# Mem_Register_V1_0.net
KiCad netlist of a schematic drawn in EAGLE
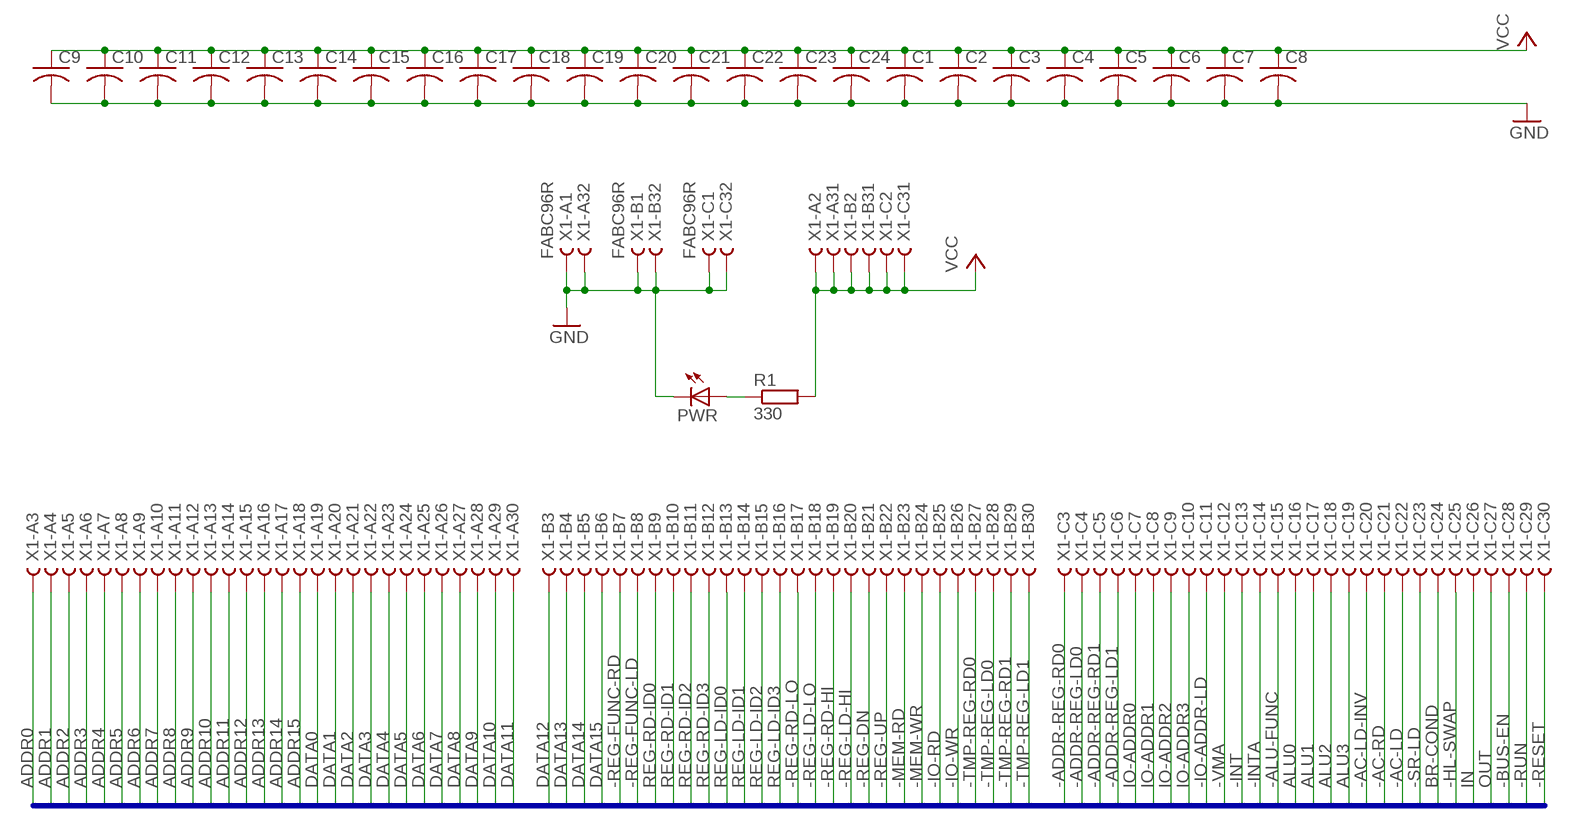
[diagram p0: schematic, sheet 1]
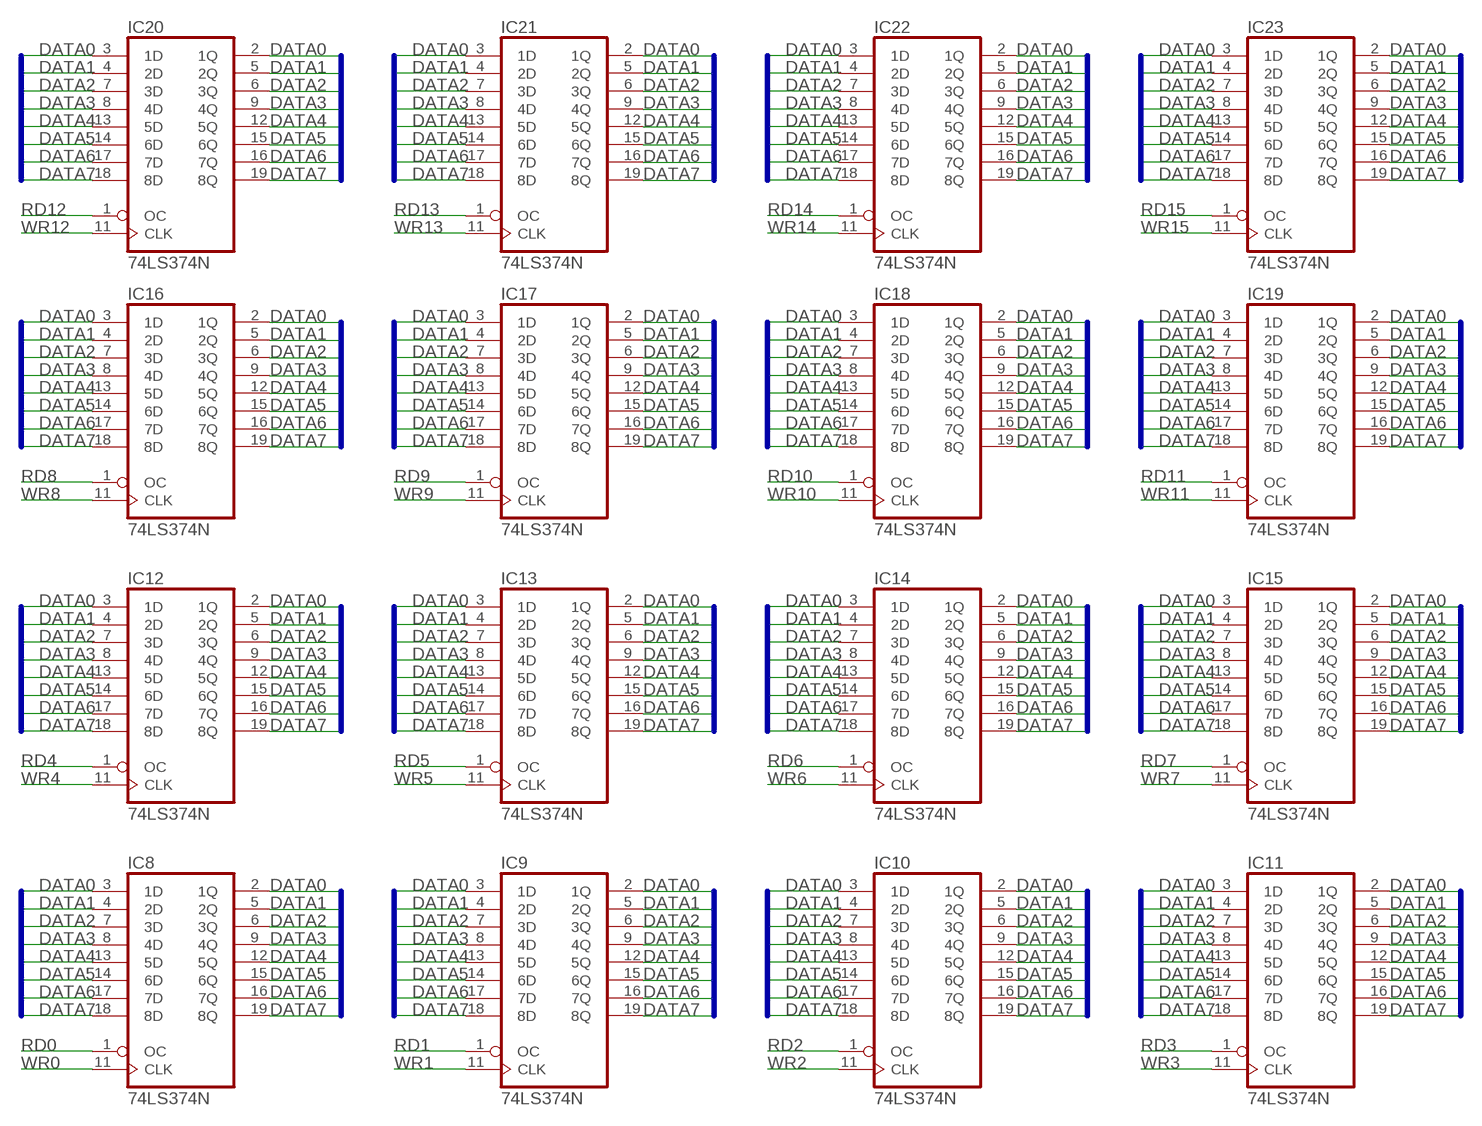
[diagram p1: schematic, sheet 2]
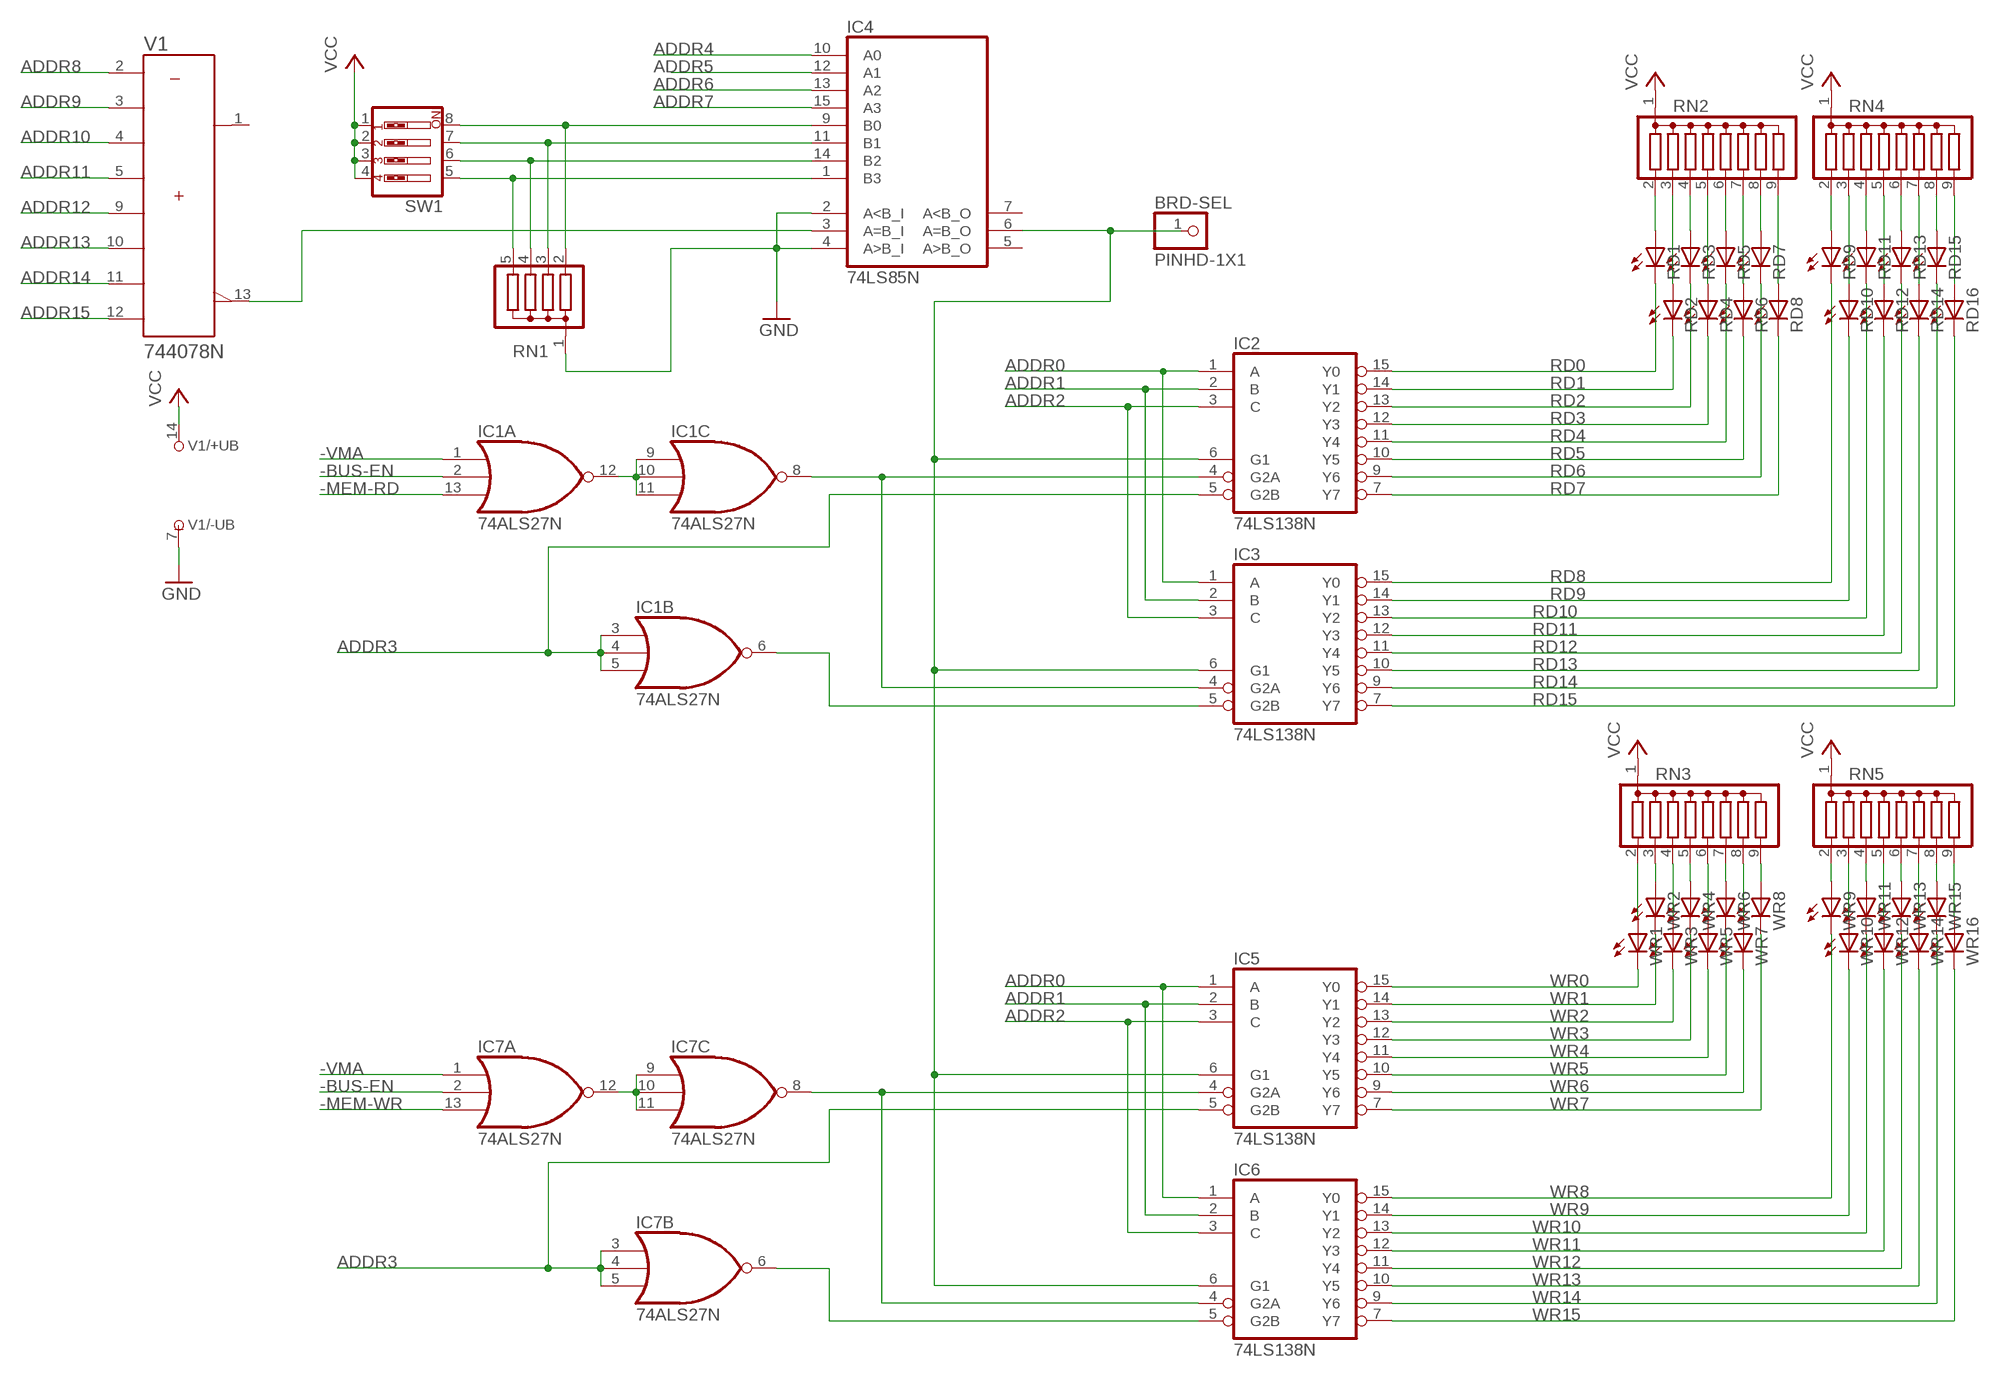
[diagram p2: schematic, sheet 3]

(export (version "E")
  (design (tool "Eeschema 10.0.6"))
  (components
    (comp (ref "C1")
      (value "C-US025-025X050")
      (footprint "eagle-import:C025-025X050")
      (libsource (lib "eagle-import") (part "C-US025-025X050"))
    )
    (comp (ref "C2")
      (value "C-US025-025X050")
      (footprint "eagle-import:C025-025X050")
      (libsource (lib "eagle-import") (part "C-US025-025X050"))
    )
    (comp (ref "C3")
      (value "C-US025-025X050")
      (footprint "eagle-import:C025-025X050")
      (libsource (lib "eagle-import") (part "C-US025-025X050"))
    )
    (comp (ref "C4")
      (value "C-US025-025X050")
      (footprint "eagle-import:C025-025X050")
      (libsource (lib "eagle-import") (part "C-US025-025X050"))
    )
    (comp (ref "C5")
      (value "C-US025-025X050")
      (footprint "eagle-import:C025-025X050")
      (libsource (lib "eagle-import") (part "C-US025-025X050"))
    )
    (comp (ref "C6")
      (value "C-US025-025X050")
      (footprint "eagle-import:C025-025X050")
      (libsource (lib "eagle-import") (part "C-US025-025X050"))
    )
    (comp (ref "C7")
      (value "C-US025-025X050")
      (footprint "eagle-import:C025-025X050")
      (libsource (lib "eagle-import") (part "C-US025-025X050"))
    )
    (comp (ref "C8")
      (value "C-US025-025X050")
      (footprint "eagle-import:C025-025X050")
      (libsource (lib "eagle-import") (part "C-US025-025X050"))
    )
    (comp (ref "C9")
      (value "C-US025-025X050")
      (footprint "eagle-import:C025-025X050")
      (libsource (lib "eagle-import") (part "C-US025-025X050"))
    )
    (comp (ref "C10")
      (value "C-US025-025X050")
      (footprint "eagle-import:C025-025X050")
      (libsource (lib "eagle-import") (part "C-US025-025X050"))
    )
    (comp (ref "C11")
      (value "C-US025-025X050")
      (footprint "eagle-import:C025-025X050")
      (libsource (lib "eagle-import") (part "C-US025-025X050"))
    )
    (comp (ref "C12")
      (value "C-US025-025X050")
      (footprint "eagle-import:C025-025X050")
      (libsource (lib "eagle-import") (part "C-US025-025X050"))
    )
    (comp (ref "C13")
      (value "C-US025-025X050")
      (footprint "eagle-import:C025-025X050")
      (libsource (lib "eagle-import") (part "C-US025-025X050"))
    )
    (comp (ref "C14")
      (value "C-US025-025X050")
      (footprint "eagle-import:C025-025X050")
      (libsource (lib "eagle-import") (part "C-US025-025X050"))
    )
    (comp (ref "C15")
      (value "C-US025-025X050")
      (footprint "eagle-import:C025-025X050")
      (libsource (lib "eagle-import") (part "C-US025-025X050"))
    )
    (comp (ref "C16")
      (value "C-US025-025X050")
      (footprint "eagle-import:C025-025X050")
      (libsource (lib "eagle-import") (part "C-US025-025X050"))
    )
    (comp (ref "C17")
      (value "C-US025-025X050")
      (footprint "eagle-import:C025-025X050")
      (libsource (lib "eagle-import") (part "C-US025-025X050"))
    )
    (comp (ref "C18")
      (value "C-US025-025X050")
      (footprint "eagle-import:C025-025X050")
      (libsource (lib "eagle-import") (part "C-US025-025X050"))
    )
    (comp (ref "C19")
      (value "C-US025-025X050")
      (footprint "eagle-import:C025-025X050")
      (libsource (lib "eagle-import") (part "C-US025-025X050"))
    )
    (comp (ref "C20")
      (value "C-US025-025X050")
      (footprint "eagle-import:C025-025X050")
      (libsource (lib "eagle-import") (part "C-US025-025X050"))
    )
    (comp (ref "C21")
      (value "C-US025-025X050")
      (footprint "eagle-import:C025-025X050")
      (libsource (lib "eagle-import") (part "C-US025-025X050"))
    )
    (comp (ref "C22")
      (value "C-US025-025X050")
      (footprint "eagle-import:C025-025X050")
      (libsource (lib "eagle-import") (part "C-US025-025X050"))
    )
    (comp (ref "C23")
      (value "C-US025-025X050")
      (footprint "eagle-import:C025-025X050")
      (libsource (lib "eagle-import") (part "C-US025-025X050"))
    )
    (comp (ref "C24")
      (value "C-US025-025X050")
      (footprint "eagle-import:C025-025X050")
      (libsource (lib "eagle-import") (part "C-US025-025X050"))
    )
    (comp (ref "PWR")
      (value "LED5MM")
      (footprint "eagle-import:LED5MM")
      (libsource (lib "eagle-import") (part "led_LED5MM"))
    )
    (comp (ref "R1")
      (value "330")
      (footprint "eagle-import:0207_10")
      (libsource (lib "eagle-import") (part "R0207/10"))
    )
    (comp (ref "X1")
      (value "FABC96R")
      (footprint "eagle-import:FABC96R")
      (libsource (lib "eagle-import") (part "FABC96R"))
    )
    (comp (ref "IC8")
      (value "74LS374N")
      (footprint "eagle-import:DIL20")
      (libsource (lib "eagle-import") (part "74374NLS"))
    )
    (comp (ref "IC9")
      (value "74LS374N")
      (footprint "eagle-import:DIL20")
      (libsource (lib "eagle-import") (part "74374NLS"))
    )
    (comp (ref "IC10")
      (value "74LS374N")
      (footprint "eagle-import:DIL20")
      (libsource (lib "eagle-import") (part "74374NLS"))
    )
    (comp (ref "IC11")
      (value "74LS374N")
      (footprint "eagle-import:DIL20")
      (libsource (lib "eagle-import") (part "74374NLS"))
    )
    (comp (ref "IC12")
      (value "74LS374N")
      (footprint "eagle-import:DIL20")
      (libsource (lib "eagle-import") (part "74374NLS"))
    )
    (comp (ref "IC13")
      (value "74LS374N")
      (footprint "eagle-import:DIL20")
      (libsource (lib "eagle-import") (part "74374NLS"))
    )
    (comp (ref "IC14")
      (value "74LS374N")
      (footprint "eagle-import:DIL20")
      (libsource (lib "eagle-import") (part "74374NLS"))
    )
    (comp (ref "IC15")
      (value "74LS374N")
      (footprint "eagle-import:DIL20")
      (libsource (lib "eagle-import") (part "74374NLS"))
    )
    (comp (ref "IC16")
      (value "74LS374N")
      (footprint "eagle-import:DIL20")
      (libsource (lib "eagle-import") (part "74374NLS"))
    )
    (comp (ref "IC17")
      (value "74LS374N")
      (footprint "eagle-import:DIL20")
      (libsource (lib "eagle-import") (part "74374NLS"))
    )
    (comp (ref "IC18")
      (value "74LS374N")
      (footprint "eagle-import:DIL20")
      (libsource (lib "eagle-import") (part "74374NLS"))
    )
    (comp (ref "IC19")
      (value "74LS374N")
      (footprint "eagle-import:DIL20")
      (libsource (lib "eagle-import") (part "74374NLS"))
    )
    (comp (ref "IC20")
      (value "74LS374N")
      (footprint "eagle-import:DIL20")
      (libsource (lib "eagle-import") (part "74374NLS"))
    )
    (comp (ref "IC21")
      (value "74LS374N")
      (footprint "eagle-import:DIL20")
      (libsource (lib "eagle-import") (part "74374NLS"))
    )
    (comp (ref "IC22")
      (value "74LS374N")
      (footprint "eagle-import:DIL20")
      (libsource (lib "eagle-import") (part "74374NLS"))
    )
    (comp (ref "IC23")
      (value "74LS374N")
      (footprint "eagle-import:DIL20")
      (libsource (lib "eagle-import") (part "74374NLS"))
    )
    (comp (ref "BRD-SEL")
      (value "PINHD-1X1")
      (footprint "eagle-import:1X01")
      (libsource (lib "eagle-import") (part "PINHD-1X1"))
    )
    (comp (ref "IC1")
      (value "74ALS27N")
      (footprint "eagle-import:DIL14")
      (libsource (lib "eagle-import") (part "7427NALS"))
    )
    (comp (ref "IC2")
      (value "74LS138N")
      (footprint "eagle-import:DIL16")
      (libsource (lib "eagle-import") (part "74138NLS"))
    )
    (comp (ref "IC3")
      (value "74LS138N")
      (footprint "eagle-import:DIL16")
      (libsource (lib "eagle-import") (part "74138NLS"))
    )
    (comp (ref "IC4")
      (value "74LS85N")
      (footprint "eagle-import:DIL16")
      (libsource (lib "eagle-import") (part "7485NLS"))
    )
    (comp (ref "IC5")
      (value "74LS138N")
      (footprint "eagle-import:DIL16")
      (libsource (lib "eagle-import") (part "74138NLS"))
    )
    (comp (ref "IC6")
      (value "74LS138N")
      (footprint "eagle-import:DIL16")
      (libsource (lib "eagle-import") (part "74138NLS"))
    )
    (comp (ref "IC7")
      (value "74ALS27N")
      (footprint "eagle-import:DIL14")
      (libsource (lib "eagle-import") (part "7427NALS"))
    )
    (comp (ref "RD1")
      (value "LED3MM")
      (footprint "eagle-import:LED3MM")
      (libsource (lib "eagle-import") (part "LED3MM"))
    )
    (comp (ref "RD2")
      (value "LED3MM")
      (footprint "eagle-import:LED3MM")
      (libsource (lib "eagle-import") (part "LED3MM"))
    )
    (comp (ref "RD3")
      (value "LED3MM")
      (footprint "eagle-import:LED3MM")
      (libsource (lib "eagle-import") (part "LED3MM"))
    )
    (comp (ref "RD4")
      (value "LED3MM")
      (footprint "eagle-import:LED3MM")
      (libsource (lib "eagle-import") (part "LED3MM"))
    )
    (comp (ref "RD5")
      (value "LED3MM")
      (footprint "eagle-import:LED3MM")
      (libsource (lib "eagle-import") (part "LED3MM"))
    )
    (comp (ref "RD6")
      (value "LED3MM")
      (footprint "eagle-import:LED3MM")
      (libsource (lib "eagle-import") (part "LED3MM"))
    )
    (comp (ref "RD7")
      (value "LED3MM")
      (footprint "eagle-import:LED3MM")
      (libsource (lib "eagle-import") (part "LED3MM"))
    )
    (comp (ref "RD8")
      (value "LED3MM")
      (footprint "eagle-import:LED3MM")
      (libsource (lib "eagle-import") (part "LED3MM"))
    )
    (comp (ref "RD9")
      (value "LED3MM")
      (footprint "eagle-import:LED3MM")
      (libsource (lib "eagle-import") (part "LED3MM"))
    )
    (comp (ref "RD10")
      (value "LED3MM")
      (footprint "eagle-import:LED3MM")
      (libsource (lib "eagle-import") (part "LED3MM"))
    )
    (comp (ref "RD11")
      (value "LED3MM")
      (footprint "eagle-import:LED3MM")
      (libsource (lib "eagle-import") (part "LED3MM"))
    )
    (comp (ref "RD12")
      (value "LED3MM")
      (footprint "eagle-import:LED3MM")
      (libsource (lib "eagle-import") (part "LED3MM"))
    )
    (comp (ref "RD13")
      (value "LED3MM")
      (footprint "eagle-import:LED3MM")
      (libsource (lib "eagle-import") (part "LED3MM"))
    )
    (comp (ref "RD14")
      (value "LED3MM")
      (footprint "eagle-import:LED3MM")
      (libsource (lib "eagle-import") (part "LED3MM"))
    )
    (comp (ref "RD15")
      (value "LED3MM")
      (footprint "eagle-import:LED3MM")
      (libsource (lib "eagle-import") (part "LED3MM"))
    )
    (comp (ref "RD16")
      (value "LED3MM")
      (footprint "eagle-import:LED3MM")
      (libsource (lib "eagle-import") (part "LED3MM"))
    )
    (comp (ref "RN1")
      (value "G04R")
      (footprint "eagle-import:SIL5")
      (libsource (lib "eagle-import") (part "G04R"))
    )
    (comp (ref "RN2")
      (value "G08R")
      (footprint "eagle-import:SIL9")
      (libsource (lib "eagle-import") (part "G08R"))
    )
    (comp (ref "RN3")
      (value "G08R")
      (footprint "eagle-import:SIL9")
      (libsource (lib "eagle-import") (part "G08R"))
    )
    (comp (ref "RN4")
      (value "G08R")
      (footprint "eagle-import:SIL9")
      (libsource (lib "eagle-import") (part "G08R"))
    )
    (comp (ref "RN5")
      (value "G08R")
      (footprint "eagle-import:SIL9")
      (libsource (lib "eagle-import") (part "G08R"))
    )
    (comp (ref "SW1")
      (value "SW_DIP-4")
      (footprint "eagle-import:EDG-04")
      (libsource (lib "eagle-import") (part "SW_DIP-4"))
    )
    (comp (ref "V1")
      (value "744078N")
      (footprint "eagle-import:DIL14")
      (libsource (lib "eagle-import") (part "744078N"))
    )
    (comp (ref "WR1")
      (value "LED3MM")
      (footprint "eagle-import:LED3MM")
      (libsource (lib "eagle-import") (part "LED3MM"))
    )
    (comp (ref "WR2")
      (value "LED3MM")
      (footprint "eagle-import:LED3MM")
      (libsource (lib "eagle-import") (part "LED3MM"))
    )
    (comp (ref "WR3")
      (value "LED3MM")
      (footprint "eagle-import:LED3MM")
      (libsource (lib "eagle-import") (part "LED3MM"))
    )
    (comp (ref "WR4")
      (value "LED3MM")
      (footprint "eagle-import:LED3MM")
      (libsource (lib "eagle-import") (part "LED3MM"))
    )
    (comp (ref "WR5")
      (value "LED3MM")
      (footprint "eagle-import:LED3MM")
      (libsource (lib "eagle-import") (part "LED3MM"))
    )
    (comp (ref "WR6")
      (value "LED3MM")
      (footprint "eagle-import:LED3MM")
      (libsource (lib "eagle-import") (part "LED3MM"))
    )
    (comp (ref "WR7")
      (value "LED3MM")
      (footprint "eagle-import:LED3MM")
      (libsource (lib "eagle-import") (part "LED3MM"))
    )
    (comp (ref "WR8")
      (value "LED3MM")
      (footprint "eagle-import:LED3MM")
      (libsource (lib "eagle-import") (part "LED3MM"))
    )
    (comp (ref "WR9")
      (value "LED3MM")
      (footprint "eagle-import:LED3MM")
      (libsource (lib "eagle-import") (part "LED3MM"))
    )
    (comp (ref "WR10")
      (value "LED3MM")
      (footprint "eagle-import:LED3MM")
      (libsource (lib "eagle-import") (part "LED3MM"))
    )
    (comp (ref "WR11")
      (value "LED3MM")
      (footprint "eagle-import:LED3MM")
      (libsource (lib "eagle-import") (part "LED3MM"))
    )
    (comp (ref "WR12")
      (value "LED3MM")
      (footprint "eagle-import:LED3MM")
      (libsource (lib "eagle-import") (part "LED3MM"))
    )
    (comp (ref "WR13")
      (value "LED3MM")
      (footprint "eagle-import:LED3MM")
      (libsource (lib "eagle-import") (part "LED3MM"))
    )
    (comp (ref "WR14")
      (value "LED3MM")
      (footprint "eagle-import:LED3MM")
      (libsource (lib "eagle-import") (part "LED3MM"))
    )
    (comp (ref "WR15")
      (value "LED3MM")
      (footprint "eagle-import:LED3MM")
      (libsource (lib "eagle-import") (part "LED3MM"))
    )
    (comp (ref "WR16")
      (value "LED3MM")
      (footprint "eagle-import:LED3MM")
      (libsource (lib "eagle-import") (part "LED3MM"))
    )
  )
  (nets
    (net (code "1") (name "-AC-LD") (class "Default")
      (node (ref "X1") (pin "C22") (pinfunction "B_C22") (pintype "passive"))
    )
    (net (code "2") (name "-AC-LD-INV") (class "Default")
      (node (ref "X1") (pin "C20") (pinfunction "B_C20") (pintype "passive"))
    )
    (net (code "3") (name "-AC-RD") (class "Default")
      (node (ref "X1") (pin "C21") (pinfunction "B_C21") (pintype "passive"))
    )
    (net (code "4") (name "-ADDR-REG-LD0") (class "Default")
      (node (ref "X1") (pin "C4") (pinfunction "B_C4") (pintype "passive"))
    )
    (net (code "5") (name "-ADDR-REG-LD1") (class "Default")
      (node (ref "X1") (pin "C6") (pinfunction "B_C6") (pintype "passive"))
    )
    (net (code "6") (name "-ADDR-REG-RD0") (class "Default")
      (node (ref "X1") (pin "C3") (pinfunction "B_C3") (pintype "passive"))
    )
    (net (code "7") (name "-ADDR-REG-RD1") (class "Default")
      (node (ref "X1") (pin "C5") (pinfunction "B_C5") (pintype "passive"))
    )
    (net (code "8") (name "-ALU-FUNC") (class "Default")
      (node (ref "X1") (pin "C15") (pinfunction "B_C15") (pintype "passive"))
    )
    (net (code "9") (name "-BUS-EN") (class "Default")
      (node (ref "IC1") (pin "2") (pinfunction "I1_2") (pintype "input"))
      (node (ref "IC7") (pin "2") (pinfunction "I1_2") (pintype "input"))
      (node (ref "X1") (pin "C28") (pinfunction "B_C28") (pintype "passive"))
    )
    (net (code "10") (name "-HL-SWAP") (class "Default")
      (node (ref "X1") (pin "C25") (pinfunction "B_C25") (pintype "passive"))
    )
    (net (code "11") (name "-INT") (class "Default")
      (node (ref "X1") (pin "C13") (pinfunction "B_C13") (pintype "passive"))
    )
    (net (code "12") (name "-INTA") (class "Default")
      (node (ref "X1") (pin "C14") (pinfunction "B_C14") (pintype "passive"))
    )
    (net (code "13") (name "-IO-ADDR-LD") (class "Default")
      (node (ref "X1") (pin "C11") (pinfunction "B_C11") (pintype "passive"))
    )
    (net (code "14") (name "-IO-RD") (class "Default")
      (node (ref "X1") (pin "B25") (pinfunction "B_B25") (pintype "passive"))
    )
    (net (code "15") (name "-IO-WR") (class "Default")
      (node (ref "X1") (pin "B26") (pinfunction "B_B26") (pintype "passive"))
    )
    (net (code "16") (name "-MEM-RD") (class "Default")
      (node (ref "IC1") (pin "13") (pinfunction "I2_13") (pintype "input"))
      (node (ref "X1") (pin "B23") (pinfunction "B_B23") (pintype "passive"))
    )
    (net (code "17") (name "-MEM-WR") (class "Default")
      (node (ref "IC7") (pin "13") (pinfunction "I2_13") (pintype "input"))
      (node (ref "X1") (pin "B24") (pinfunction "B_B24") (pintype "passive"))
    )
    (net (code "18") (name "-REG-DN") (class "Default")
      (node (ref "X1") (pin "B21") (pinfunction "B_B21") (pintype "passive"))
    )
    (net (code "19") (name "-REG-FUNC-LD") (class "Default")
      (node (ref "X1") (pin "B8") (pinfunction "B_B8") (pintype "passive"))
    )
    (net (code "20") (name "-REG-FUNC-RD") (class "Default")
      (node (ref "X1") (pin "B7") (pinfunction "B_B7") (pintype "passive"))
    )
    (net (code "21") (name "-REG-LD-HI") (class "Default")
      (node (ref "X1") (pin "B20") (pinfunction "B_B20") (pintype "passive"))
    )
    (net (code "22") (name "-REG-LD-LO") (class "Default")
      (node (ref "X1") (pin "B18") (pinfunction "B_B18") (pintype "passive"))
    )
    (net (code "23") (name "-REG-RD-HI") (class "Default")
      (node (ref "X1") (pin "B19") (pinfunction "B_B19") (pintype "passive"))
    )
    (net (code "24") (name "-REG-RD-LO") (class "Default")
      (node (ref "X1") (pin "B17") (pinfunction "B_B17") (pintype "passive"))
    )
    (net (code "25") (name "-REG-UP") (class "Default")
      (node (ref "X1") (pin "B22") (pinfunction "B_B22") (pintype "passive"))
    )
    (net (code "26") (name "-RESET") (class "Default")
      (node (ref "X1") (pin "C30") (pinfunction "B_C30") (pintype "passive"))
    )
    (net (code "27") (name "-RUN") (class "Default")
      (node (ref "X1") (pin "C29") (pinfunction "B_C29") (pintype "passive"))
    )
    (net (code "28") (name "-SR-LD") (class "Default")
      (node (ref "X1") (pin "C23") (pinfunction "B_C23") (pintype "passive"))
    )
    (net (code "29") (name "-TMP-REG-LD0") (class "Default")
      (node (ref "X1") (pin "B28") (pinfunction "B_B28") (pintype "passive"))
    )
    (net (code "30") (name "-TMP-REG-LD1") (class "Default")
      (node (ref "X1") (pin "B30") (pinfunction "B_B30") (pintype "passive"))
    )
    (net (code "31") (name "-TMP-REG-RD0") (class "Default")
      (node (ref "X1") (pin "B27") (pinfunction "B_B27") (pintype "passive"))
    )
    (net (code "32") (name "-TMP-REG-RD1") (class "Default")
      (node (ref "X1") (pin "B29") (pinfunction "B_B29") (pintype "passive"))
    )
    (net (code "33") (name "-VMA") (class "Default")
      (node (ref "IC1") (pin "1") (pinfunction "I0_1") (pintype "input"))
      (node (ref "IC7") (pin "1") (pinfunction "I0_1") (pintype "input"))
      (node (ref "X1") (pin "C12") (pinfunction "B_C12") (pintype "passive"))
    )
    (net (code "34") (name "ADDR0") (class "Default")
      (node (ref "IC2") (pin "1") (pinfunction "A_1") (pintype "input"))
      (node (ref "IC3") (pin "1") (pinfunction "A_1") (pintype "input"))
      (node (ref "IC5") (pin "1") (pinfunction "A_1") (pintype "input"))
      (node (ref "IC6") (pin "1") (pinfunction "A_1") (pintype "input"))
      (node (ref "X1") (pin "A3") (pinfunction "B_A3") (pintype "passive"))
    )
    (net (code "35") (name "ADDR1") (class "Default")
      (node (ref "IC2") (pin "2") (pinfunction "B_2") (pintype "input"))
      (node (ref "IC3") (pin "2") (pinfunction "B_2") (pintype "input"))
      (node (ref "IC5") (pin "2") (pinfunction "B_2") (pintype "input"))
      (node (ref "IC6") (pin "2") (pinfunction "B_2") (pintype "input"))
      (node (ref "X1") (pin "A4") (pinfunction "B_A4") (pintype "passive"))
    )
    (net (code "36") (name "ADDR2") (class "Default")
      (node (ref "IC2") (pin "3") (pinfunction "C_3") (pintype "input"))
      (node (ref "IC3") (pin "3") (pinfunction "C_3") (pintype "input"))
      (node (ref "IC5") (pin "3") (pinfunction "C_3") (pintype "input"))
      (node (ref "IC6") (pin "3") (pinfunction "C_3") (pintype "input"))
      (node (ref "X1") (pin "A5") (pinfunction "B_A5") (pintype "passive"))
    )
    (net (code "37") (name "ADDR3") (class "Default")
      (node (ref "IC1") (pin "3") (pinfunction "I0_3") (pintype "input"))
      (node (ref "IC1") (pin "4") (pinfunction "I1_4") (pintype "input"))
      (node (ref "IC1") (pin "5") (pinfunction "I2_5") (pintype "input"))
      (node (ref "IC2") (pin "5") (pinfunction "G2B_5") (pintype "input"))
      (node (ref "IC5") (pin "5") (pinfunction "G2B_5") (pintype "input"))
      (node (ref "IC7") (pin "3") (pinfunction "I0_3") (pintype "input"))
      (node (ref "IC7") (pin "4") (pinfunction "I1_4") (pintype "input"))
      (node (ref "IC7") (pin "5") (pinfunction "I2_5") (pintype "input"))
      (node (ref "X1") (pin "A6") (pinfunction "B_A6") (pintype "passive"))
    )
    (net (code "38") (name "ADDR4") (class "Default")
      (node (ref "IC4") (pin "10") (pinfunction "A0_10") (pintype "input"))
      (node (ref "X1") (pin "A7") (pinfunction "B_A7") (pintype "passive"))
    )
    (net (code "39") (name "ADDR5") (class "Default")
      (node (ref "IC4") (pin "12") (pinfunction "A1_12") (pintype "input"))
      (node (ref "X1") (pin "A8") (pinfunction "B_A8") (pintype "passive"))
    )
    (net (code "40") (name "ADDR6") (class "Default")
      (node (ref "IC4") (pin "13") (pinfunction "A2_13") (pintype "input"))
      (node (ref "X1") (pin "A9") (pinfunction "B_A9") (pintype "passive"))
    )
    (net (code "41") (name "ADDR7") (class "Default")
      (node (ref "IC4") (pin "15") (pinfunction "A3_15") (pintype "input"))
      (node (ref "X1") (pin "A10") (pinfunction "B_A10") (pintype "passive"))
    )
    (net (code "42") (name "ADDR8") (class "Default")
      (node (ref "V1") (pin "2") (pinfunction "A_2") (pintype "input"))
      (node (ref "X1") (pin "A11") (pinfunction "B_A11") (pintype "passive"))
    )
    (net (code "43") (name "ADDR9") (class "Default")
      (node (ref "V1") (pin "3") (pinfunction "B_3") (pintype "input"))
      (node (ref "X1") (pin "A12") (pinfunction "B_A12") (pintype "passive"))
    )
    (net (code "44") (name "ADDR10") (class "Default")
      (node (ref "V1") (pin "4") (pinfunction "C_4") (pintype "input"))
      (node (ref "X1") (pin "A13") (pinfunction "B_A13") (pintype "passive"))
    )
    (net (code "45") (name "ADDR11") (class "Default")
      (node (ref "V1") (pin "5") (pinfunction "D_5") (pintype "input"))
      (node (ref "X1") (pin "A14") (pinfunction "B_A14") (pintype "passive"))
    )
    (net (code "46") (name "ADDR12") (class "Default")
      (node (ref "V1") (pin "9") (pinfunction "E_9") (pintype "input"))
      (node (ref "X1") (pin "A15") (pinfunction "B_A15") (pintype "passive"))
    )
    (net (code "47") (name "ADDR13") (class "Default")
      (node (ref "V1") (pin "10") (pinfunction "F_10") (pintype "input"))
      (node (ref "X1") (pin "A16") (pinfunction "B_A16") (pintype "passive"))
    )
    (net (code "48") (name "ADDR14") (class "Default")
      (node (ref "V1") (pin "11") (pinfunction "G_11") (pintype "input"))
      (node (ref "X1") (pin "A17") (pinfunction "B_A17") (pintype "passive"))
    )
    (net (code "49") (name "ADDR15") (class "Default")
      (node (ref "V1") (pin "12") (pinfunction "H_12") (pintype "input"))
      (node (ref "X1") (pin "A18") (pinfunction "B_A18") (pintype "passive"))
    )
    (net (code "50") (name "ALU0") (class "Default")
      (node (ref "X1") (pin "C16") (pinfunction "B_C16") (pintype "passive"))
    )
    (net (code "51") (name "ALU1") (class "Default")
      (node (ref "X1") (pin "C17") (pinfunction "B_C17") (pintype "passive"))
    )
    (net (code "52") (name "ALU2") (class "Default")
      (node (ref "X1") (pin "C18") (pinfunction "B_C18") (pintype "passive"))
    )
    (net (code "53") (name "ALU3") (class "Default")
      (node (ref "X1") (pin "C19") (pinfunction "B_C19") (pintype "passive"))
    )
    (net (code "54") (name "BR-COND") (class "Default")
      (node (ref "X1") (pin "C24") (pinfunction "B_C24") (pintype "passive"))
    )
    (net (code "55") (name "DATA0") (class "Default")
      (node (ref "IC10") (pin "2") (pinfunction "1Q_2") (pintype "tri_state"))
      (node (ref "IC10") (pin "3") (pinfunction "1D_3") (pintype "input"))
      (node (ref "IC11") (pin "2") (pinfunction "1Q_2") (pintype "tri_state"))
      (node (ref "IC11") (pin "3") (pinfunction "1D_3") (pintype "input"))
      (node (ref "IC12") (pin "2") (pinfunction "1Q_2") (pintype "tri_state"))
      (node (ref "IC12") (pin "3") (pinfunction "1D_3") (pintype "input"))
      (node (ref "IC13") (pin "2") (pinfunction "1Q_2") (pintype "tri_state"))
      (node (ref "IC13") (pin "3") (pinfunction "1D_3") (pintype "input"))
      (node (ref "IC14") (pin "2") (pinfunction "1Q_2") (pintype "tri_state"))
      (node (ref "IC14") (pin "3") (pinfunction "1D_3") (pintype "input"))
      (node (ref "IC15") (pin "2") (pinfunction "1Q_2") (pintype "tri_state"))
      (node (ref "IC15") (pin "3") (pinfunction "1D_3") (pintype "input"))
      (node (ref "IC16") (pin "2") (pinfunction "1Q_2") (pintype "tri_state"))
      (node (ref "IC16") (pin "3") (pinfunction "1D_3") (pintype "input"))
      (node (ref "IC17") (pin "2") (pinfunction "1Q_2") (pintype "tri_state"))
      (node (ref "IC17") (pin "3") (pinfunction "1D_3") (pintype "input"))
      (node (ref "IC18") (pin "2") (pinfunction "1Q_2") (pintype "tri_state"))
      (node (ref "IC18") (pin "3") (pinfunction "1D_3") (pintype "input"))
      (node (ref "IC19") (pin "2") (pinfunction "1Q_2") (pintype "tri_state"))
      (node (ref "IC19") (pin "3") (pinfunction "1D_3") (pintype "input"))
      (node (ref "IC20") (pin "2") (pinfunction "1Q_2") (pintype "tri_state"))
      (node (ref "IC20") (pin "3") (pinfunction "1D_3") (pintype "input"))
      (node (ref "IC21") (pin "2") (pinfunction "1Q_2") (pintype "tri_state"))
      (node (ref "IC21") (pin "3") (pinfunction "1D_3") (pintype "input"))
      (node (ref "IC22") (pin "2") (pinfunction "1Q_2") (pintype "tri_state"))
      (node (ref "IC22") (pin "3") (pinfunction "1D_3") (pintype "input"))
      (node (ref "IC23") (pin "2") (pinfunction "1Q_2") (pintype "tri_state"))
      (node (ref "IC23") (pin "3") (pinfunction "1D_3") (pintype "input"))
      (node (ref "IC8") (pin "2") (pinfunction "1Q_2") (pintype "tri_state"))
      (node (ref "IC8") (pin "3") (pinfunction "1D_3") (pintype "input"))
      (node (ref "IC9") (pin "2") (pinfunction "1Q_2") (pintype "tri_state"))
      (node (ref "IC9") (pin "3") (pinfunction "1D_3") (pintype "input"))
      (node (ref "X1") (pin "A19") (pinfunction "B_A19") (pintype "passive"))
    )
    (net (code "56") (name "DATA1") (class "Default")
      (node (ref "IC10") (pin "4") (pinfunction "2D_4") (pintype "input"))
      (node (ref "IC10") (pin "5") (pinfunction "2Q_5") (pintype "tri_state"))
      (node (ref "IC11") (pin "4") (pinfunction "2D_4") (pintype "input"))
      (node (ref "IC11") (pin "5") (pinfunction "2Q_5") (pintype "tri_state"))
      (node (ref "IC12") (pin "4") (pinfunction "2D_4") (pintype "input"))
      (node (ref "IC12") (pin "5") (pinfunction "2Q_5") (pintype "tri_state"))
      (node (ref "IC13") (pin "4") (pinfunction "2D_4") (pintype "input"))
      (node (ref "IC13") (pin "5") (pinfunction "2Q_5") (pintype "tri_state"))
      (node (ref "IC14") (pin "4") (pinfunction "2D_4") (pintype "input"))
      (node (ref "IC14") (pin "5") (pinfunction "2Q_5") (pintype "tri_state"))
      (node (ref "IC15") (pin "4") (pinfunction "2D_4") (pintype "input"))
      (node (ref "IC15") (pin "5") (pinfunction "2Q_5") (pintype "tri_state"))
      (node (ref "IC16") (pin "4") (pinfunction "2D_4") (pintype "input"))
      (node (ref "IC16") (pin "5") (pinfunction "2Q_5") (pintype "tri_state"))
      (node (ref "IC17") (pin "4") (pinfunction "2D_4") (pintype "input"))
      (node (ref "IC17") (pin "5") (pinfunction "2Q_5") (pintype "tri_state"))
      (node (ref "IC18") (pin "4") (pinfunction "2D_4") (pintype "input"))
      (node (ref "IC18") (pin "5") (pinfunction "2Q_5") (pintype "tri_state"))
      (node (ref "IC19") (pin "4") (pinfunction "2D_4") (pintype "input"))
      (node (ref "IC19") (pin "5") (pinfunction "2Q_5") (pintype "tri_state"))
      (node (ref "IC20") (pin "4") (pinfunction "2D_4") (pintype "input"))
      (node (ref "IC20") (pin "5") (pinfunction "2Q_5") (pintype "tri_state"))
      (node (ref "IC21") (pin "4") (pinfunction "2D_4") (pintype "input"))
      (node (ref "IC21") (pin "5") (pinfunction "2Q_5") (pintype "tri_state"))
      (node (ref "IC22") (pin "4") (pinfunction "2D_4") (pintype "input"))
      (node (ref "IC22") (pin "5") (pinfunction "2Q_5") (pintype "tri_state"))
      (node (ref "IC23") (pin "4") (pinfunction "2D_4") (pintype "input"))
      (node (ref "IC23") (pin "5") (pinfunction "2Q_5") (pintype "tri_state"))
      (node (ref "IC8") (pin "4") (pinfunction "2D_4") (pintype "input"))
      (node (ref "IC8") (pin "5") (pinfunction "2Q_5") (pintype "tri_state"))
      (node (ref "IC9") (pin "4") (pinfunction "2D_4") (pintype "input"))
      (node (ref "IC9") (pin "5") (pinfunction "2Q_5") (pintype "tri_state"))
      (node (ref "X1") (pin "A20") (pinfunction "B_A20") (pintype "passive"))
    )
    (net (code "57") (name "DATA2") (class "Default")
      (node (ref "IC10") (pin "6") (pinfunction "3Q_6") (pintype "tri_state"))
      (node (ref "IC10") (pin "7") (pinfunction "3D_7") (pintype "input"))
      (node (ref "IC11") (pin "6") (pinfunction "3Q_6") (pintype "tri_state"))
      (node (ref "IC11") (pin "7") (pinfunction "3D_7") (pintype "input"))
      (node (ref "IC12") (pin "6") (pinfunction "3Q_6") (pintype "tri_state"))
      (node (ref "IC12") (pin "7") (pinfunction "3D_7") (pintype "input"))
      (node (ref "IC13") (pin "6") (pinfunction "3Q_6") (pintype "tri_state"))
      (node (ref "IC13") (pin "7") (pinfunction "3D_7") (pintype "input"))
      (node (ref "IC14") (pin "6") (pinfunction "3Q_6") (pintype "tri_state"))
      (node (ref "IC14") (pin "7") (pinfunction "3D_7") (pintype "input"))
      (node (ref "IC15") (pin "6") (pinfunction "3Q_6") (pintype "tri_state"))
      (node (ref "IC15") (pin "7") (pinfunction "3D_7") (pintype "input"))
      (node (ref "IC16") (pin "6") (pinfunction "3Q_6") (pintype "tri_state"))
      (node (ref "IC16") (pin "7") (pinfunction "3D_7") (pintype "input"))
      (node (ref "IC17") (pin "6") (pinfunction "3Q_6") (pintype "tri_state"))
      (node (ref "IC17") (pin "7") (pinfunction "3D_7") (pintype "input"))
      (node (ref "IC18") (pin "6") (pinfunction "3Q_6") (pintype "tri_state"))
      (node (ref "IC18") (pin "7") (pinfunction "3D_7") (pintype "input"))
      (node (ref "IC19") (pin "6") (pinfunction "3Q_6") (pintype "tri_state"))
      (node (ref "IC19") (pin "7") (pinfunction "3D_7") (pintype "input"))
      (node (ref "IC20") (pin "6") (pinfunction "3Q_6") (pintype "tri_state"))
      (node (ref "IC20") (pin "7") (pinfunction "3D_7") (pintype "input"))
      (node (ref "IC21") (pin "6") (pinfunction "3Q_6") (pintype "tri_state"))
      (node (ref "IC21") (pin "7") (pinfunction "3D_7") (pintype "input"))
      (node (ref "IC22") (pin "6") (pinfunction "3Q_6") (pintype "tri_state"))
      (node (ref "IC22") (pin "7") (pinfunction "3D_7") (pintype "input"))
      (node (ref "IC23") (pin "6") (pinfunction "3Q_6") (pintype "tri_state"))
      (node (ref "IC23") (pin "7") (pinfunction "3D_7") (pintype "input"))
      (node (ref "IC8") (pin "6") (pinfunction "3Q_6") (pintype "tri_state"))
      (node (ref "IC8") (pin "7") (pinfunction "3D_7") (pintype "input"))
      (node (ref "IC9") (pin "6") (pinfunction "3Q_6") (pintype "tri_state"))
      (node (ref "IC9") (pin "7") (pinfunction "3D_7") (pintype "input"))
      (node (ref "X1") (pin "A21") (pinfunction "B_A21") (pintype "passive"))
    )
    (net (code "58") (name "DATA3") (class "Default")
      (node (ref "IC10") (pin "8") (pinfunction "4D_8") (pintype "input"))
      (node (ref "IC10") (pin "9") (pinfunction "4Q_9") (pintype "tri_state"))
      (node (ref "IC11") (pin "8") (pinfunction "4D_8") (pintype "input"))
      (node (ref "IC11") (pin "9") (pinfunction "4Q_9") (pintype "tri_state"))
      (node (ref "IC12") (pin "8") (pinfunction "4D_8") (pintype "input"))
      (node (ref "IC12") (pin "9") (pinfunction "4Q_9") (pintype "tri_state"))
      (node (ref "IC13") (pin "8") (pinfunction "4D_8") (pintype "input"))
      (node (ref "IC13") (pin "9") (pinfunction "4Q_9") (pintype "tri_state"))
      (node (ref "IC14") (pin "8") (pinfunction "4D_8") (pintype "input"))
      (node (ref "IC14") (pin "9") (pinfunction "4Q_9") (pintype "tri_state"))
      (node (ref "IC15") (pin "8") (pinfunction "4D_8") (pintype "input"))
      (node (ref "IC15") (pin "9") (pinfunction "4Q_9") (pintype "tri_state"))
      (node (ref "IC16") (pin "8") (pinfunction "4D_8") (pintype "input"))
      (node (ref "IC16") (pin "9") (pinfunction "4Q_9") (pintype "tri_state"))
      (node (ref "IC17") (pin "8") (pinfunction "4D_8") (pintype "input"))
      (node (ref "IC17") (pin "9") (pinfunction "4Q_9") (pintype "tri_state"))
      (node (ref "IC18") (pin "8") (pinfunction "4D_8") (pintype "input"))
      (node (ref "IC18") (pin "9") (pinfunction "4Q_9") (pintype "tri_state"))
      (node (ref "IC19") (pin "8") (pinfunction "4D_8") (pintype "input"))
      (node (ref "IC19") (pin "9") (pinfunction "4Q_9") (pintype "tri_state"))
      (node (ref "IC20") (pin "8") (pinfunction "4D_8") (pintype "input"))
      (node (ref "IC20") (pin "9") (pinfunction "4Q_9") (pintype "tri_state"))
      (node (ref "IC21") (pin "8") (pinfunction "4D_8") (pintype "input"))
      (node (ref "IC21") (pin "9") (pinfunction "4Q_9") (pintype "tri_state"))
      (node (ref "IC22") (pin "8") (pinfunction "4D_8") (pintype "input"))
      (node (ref "IC22") (pin "9") (pinfunction "4Q_9") (pintype "tri_state"))
      (node (ref "IC23") (pin "8") (pinfunction "4D_8") (pintype "input"))
      (node (ref "IC23") (pin "9") (pinfunction "4Q_9") (pintype "tri_state"))
      (node (ref "IC8") (pin "8") (pinfunction "4D_8") (pintype "input"))
      (node (ref "IC8") (pin "9") (pinfunction "4Q_9") (pintype "tri_state"))
      (node (ref "IC9") (pin "8") (pinfunction "4D_8") (pintype "input"))
      (node (ref "IC9") (pin "9") (pinfunction "4Q_9") (pintype "tri_state"))
      (node (ref "X1") (pin "A22") (pinfunction "B_A22") (pintype "passive"))
    )
    (net (code "59") (name "DATA4") (class "Default")
      (node (ref "IC10") (pin "12") (pinfunction "5Q_12") (pintype "tri_state"))
      (node (ref "IC10") (pin "13") (pinfunction "5D_13") (pintype "input"))
      (node (ref "IC11") (pin "12") (pinfunction "5Q_12") (pintype "tri_state"))
      (node (ref "IC11") (pin "13") (pinfunction "5D_13") (pintype "input"))
      (node (ref "IC12") (pin "12") (pinfunction "5Q_12") (pintype "tri_state"))
      (node (ref "IC12") (pin "13") (pinfunction "5D_13") (pintype "input"))
      (node (ref "IC13") (pin "12") (pinfunction "5Q_12") (pintype "tri_state"))
      (node (ref "IC13") (pin "13") (pinfunction "5D_13") (pintype "input"))
      (node (ref "IC14") (pin "12") (pinfunction "5Q_12") (pintype "tri_state"))
      (node (ref "IC14") (pin "13") (pinfunction "5D_13") (pintype "input"))
      (node (ref "IC15") (pin "12") (pinfunction "5Q_12") (pintype "tri_state"))
      (node (ref "IC15") (pin "13") (pinfunction "5D_13") (pintype "input"))
      (node (ref "IC16") (pin "12") (pinfunction "5Q_12") (pintype "tri_state"))
      (node (ref "IC16") (pin "13") (pinfunction "5D_13") (pintype "input"))
      (node (ref "IC17") (pin "12") (pinfunction "5Q_12") (pintype "tri_state"))
      (node (ref "IC17") (pin "13") (pinfunction "5D_13") (pintype "input"))
      (node (ref "IC18") (pin "12") (pinfunction "5Q_12") (pintype "tri_state"))
      (node (ref "IC18") (pin "13") (pinfunction "5D_13") (pintype "input"))
      (node (ref "IC19") (pin "12") (pinfunction "5Q_12") (pintype "tri_state"))
      (node (ref "IC19") (pin "13") (pinfunction "5D_13") (pintype "input"))
      (node (ref "IC20") (pin "12") (pinfunction "5Q_12") (pintype "tri_state"))
      (node (ref "IC20") (pin "13") (pinfunction "5D_13") (pintype "input"))
      (node (ref "IC21") (pin "12") (pinfunction "5Q_12") (pintype "tri_state"))
      (node (ref "IC21") (pin "13") (pinfunction "5D_13") (pintype "input"))
      (node (ref "IC22") (pin "12") (pinfunction "5Q_12") (pintype "tri_state"))
      (node (ref "IC22") (pin "13") (pinfunction "5D_13") (pintype "input"))
      (node (ref "IC23") (pin "12") (pinfunction "5Q_12") (pintype "tri_state"))
      (node (ref "IC23") (pin "13") (pinfunction "5D_13") (pintype "input"))
      (node (ref "IC8") (pin "12") (pinfunction "5Q_12") (pintype "tri_state"))
      (node (ref "IC8") (pin "13") (pinfunction "5D_13") (pintype "input"))
      (node (ref "IC9") (pin "12") (pinfunction "5Q_12") (pintype "tri_state"))
      (node (ref "IC9") (pin "13") (pinfunction "5D_13") (pintype "input"))
      (node (ref "X1") (pin "A23") (pinfunction "B_A23") (pintype "passive"))
    )
    (net (code "60") (name "DATA5") (class "Default")
      (node (ref "IC10") (pin "14") (pinfunction "6D_14") (pintype "input"))
      (node (ref "IC10") (pin "15") (pinfunction "6Q_15") (pintype "tri_state"))
      (node (ref "IC11") (pin "14") (pinfunction "6D_14") (pintype "input"))
      (node (ref "IC11") (pin "15") (pinfunction "6Q_15") (pintype "tri_state"))
      (node (ref "IC12") (pin "14") (pinfunction "6D_14") (pintype "input"))
      (node (ref "IC12") (pin "15") (pinfunction "6Q_15") (pintype "tri_state"))
      (node (ref "IC13") (pin "14") (pinfunction "6D_14") (pintype "input"))
      (node (ref "IC13") (pin "15") (pinfunction "6Q_15") (pintype "tri_state"))
      (node (ref "IC14") (pin "14") (pinfunction "6D_14") (pintype "input"))
      (node (ref "IC14") (pin "15") (pinfunction "6Q_15") (pintype "tri_state"))
      (node (ref "IC15") (pin "14") (pinfunction "6D_14") (pintype "input"))
      (node (ref "IC15") (pin "15") (pinfunction "6Q_15") (pintype "tri_state"))
      (node (ref "IC16") (pin "14") (pinfunction "6D_14") (pintype "input"))
      (node (ref "IC16") (pin "15") (pinfunction "6Q_15") (pintype "tri_state"))
      (node (ref "IC17") (pin "14") (pinfunction "6D_14") (pintype "input"))
      (node (ref "IC17") (pin "15") (pinfunction "6Q_15") (pintype "tri_state"))
      (node (ref "IC18") (pin "14") (pinfunction "6D_14") (pintype "input"))
      (node (ref "IC18") (pin "15") (pinfunction "6Q_15") (pintype "tri_state"))
      (node (ref "IC19") (pin "14") (pinfunction "6D_14") (pintype "input"))
      (node (ref "IC19") (pin "15") (pinfunction "6Q_15") (pintype "tri_state"))
      (node (ref "IC20") (pin "14") (pinfunction "6D_14") (pintype "input"))
      (node (ref "IC20") (pin "15") (pinfunction "6Q_15") (pintype "tri_state"))
      (node (ref "IC21") (pin "14") (pinfunction "6D_14") (pintype "input"))
      (node (ref "IC21") (pin "15") (pinfunction "6Q_15") (pintype "tri_state"))
      (node (ref "IC22") (pin "14") (pinfunction "6D_14") (pintype "input"))
      (node (ref "IC22") (pin "15") (pinfunction "6Q_15") (pintype "tri_state"))
      (node (ref "IC23") (pin "14") (pinfunction "6D_14") (pintype "input"))
      (node (ref "IC23") (pin "15") (pinfunction "6Q_15") (pintype "tri_state"))
      (node (ref "IC8") (pin "14") (pinfunction "6D_14") (pintype "input"))
      (node (ref "IC8") (pin "15") (pinfunction "6Q_15") (pintype "tri_state"))
      (node (ref "IC9") (pin "14") (pinfunction "6D_14") (pintype "input"))
      (node (ref "IC9") (pin "15") (pinfunction "6Q_15") (pintype "tri_state"))
      (node (ref "X1") (pin "A24") (pinfunction "B_A24") (pintype "passive"))
    )
    (net (code "61") (name "DATA6") (class "Default")
      (node (ref "IC10") (pin "16") (pinfunction "7Q_16") (pintype "tri_state"))
      (node (ref "IC10") (pin "17") (pinfunction "7D_17") (pintype "input"))
      (node (ref "IC11") (pin "16") (pinfunction "7Q_16") (pintype "tri_state"))
      (node (ref "IC11") (pin "17") (pinfunction "7D_17") (pintype "input"))
      (node (ref "IC12") (pin "16") (pinfunction "7Q_16") (pintype "tri_state"))
      (node (ref "IC12") (pin "17") (pinfunction "7D_17") (pintype "input"))
      (node (ref "IC13") (pin "16") (pinfunction "7Q_16") (pintype "tri_state"))
      (node (ref "IC13") (pin "17") (pinfunction "7D_17") (pintype "input"))
      (node (ref "IC14") (pin "16") (pinfunction "7Q_16") (pintype "tri_state"))
      (node (ref "IC14") (pin "17") (pinfunction "7D_17") (pintype "input"))
      (node (ref "IC15") (pin "16") (pinfunction "7Q_16") (pintype "tri_state"))
      (node (ref "IC15") (pin "17") (pinfunction "7D_17") (pintype "input"))
      (node (ref "IC16") (pin "16") (pinfunction "7Q_16") (pintype "tri_state"))
      (node (ref "IC16") (pin "17") (pinfunction "7D_17") (pintype "input"))
      (node (ref "IC17") (pin "16") (pinfunction "7Q_16") (pintype "tri_state"))
      (node (ref "IC17") (pin "17") (pinfunction "7D_17") (pintype "input"))
      (node (ref "IC18") (pin "16") (pinfunction "7Q_16") (pintype "tri_state"))
      (node (ref "IC18") (pin "17") (pinfunction "7D_17") (pintype "input"))
      (node (ref "IC19") (pin "16") (pinfunction "7Q_16") (pintype "tri_state"))
      (node (ref "IC19") (pin "17") (pinfunction "7D_17") (pintype "input"))
      (node (ref "IC20") (pin "16") (pinfunction "7Q_16") (pintype "tri_state"))
      (node (ref "IC20") (pin "17") (pinfunction "7D_17") (pintype "input"))
      (node (ref "IC21") (pin "16") (pinfunction "7Q_16") (pintype "tri_state"))
      (node (ref "IC21") (pin "17") (pinfunction "7D_17") (pintype "input"))
      (node (ref "IC22") (pin "16") (pinfunction "7Q_16") (pintype "tri_state"))
      (node (ref "IC22") (pin "17") (pinfunction "7D_17") (pintype "input"))
      (node (ref "IC23") (pin "16") (pinfunction "7Q_16") (pintype "tri_state"))
      (node (ref "IC23") (pin "17") (pinfunction "7D_17") (pintype "input"))
      (node (ref "IC8") (pin "16") (pinfunction "7Q_16") (pintype "tri_state"))
      (node (ref "IC8") (pin "17") (pinfunction "7D_17") (pintype "input"))
      (node (ref "IC9") (pin "16") (pinfunction "7Q_16") (pintype "tri_state"))
      (node (ref "IC9") (pin "17") (pinfunction "7D_17") (pintype "input"))
      (node (ref "X1") (pin "A25") (pinfunction "B_A25") (pintype "passive"))
    )
    (net (code "62") (name "DATA7") (class "Default")
      (node (ref "IC10") (pin "18") (pinfunction "8D_18") (pintype "input"))
      (node (ref "IC10") (pin "19") (pinfunction "8Q_19") (pintype "tri_state"))
      (node (ref "IC11") (pin "18") (pinfunction "8D_18") (pintype "input"))
      (node (ref "IC11") (pin "19") (pinfunction "8Q_19") (pintype "tri_state"))
      (node (ref "IC12") (pin "18") (pinfunction "8D_18") (pintype "input"))
      (node (ref "IC12") (pin "19") (pinfunction "8Q_19") (pintype "tri_state"))
      (node (ref "IC13") (pin "18") (pinfunction "8D_18") (pintype "input"))
      (node (ref "IC13") (pin "19") (pinfunction "8Q_19") (pintype "tri_state"))
      (node (ref "IC14") (pin "18") (pinfunction "8D_18") (pintype "input"))
      (node (ref "IC14") (pin "19") (pinfunction "8Q_19") (pintype "tri_state"))
      (node (ref "IC15") (pin "18") (pinfunction "8D_18") (pintype "input"))
      (node (ref "IC15") (pin "19") (pinfunction "8Q_19") (pintype "tri_state"))
      (node (ref "IC16") (pin "18") (pinfunction "8D_18") (pintype "input"))
      (node (ref "IC16") (pin "19") (pinfunction "8Q_19") (pintype "tri_state"))
      (node (ref "IC17") (pin "18") (pinfunction "8D_18") (pintype "input"))
      (node (ref "IC17") (pin "19") (pinfunction "8Q_19") (pintype "tri_state"))
      (node (ref "IC18") (pin "18") (pinfunction "8D_18") (pintype "input"))
      (node (ref "IC18") (pin "19") (pinfunction "8Q_19") (pintype "tri_state"))
      (node (ref "IC19") (pin "18") (pinfunction "8D_18") (pintype "input"))
      (node (ref "IC19") (pin "19") (pinfunction "8Q_19") (pintype "tri_state"))
      (node (ref "IC20") (pin "18") (pinfunction "8D_18") (pintype "input"))
      (node (ref "IC20") (pin "19") (pinfunction "8Q_19") (pintype "tri_state"))
      (node (ref "IC21") (pin "18") (pinfunction "8D_18") (pintype "input"))
      (node (ref "IC21") (pin "19") (pinfunction "8Q_19") (pintype "tri_state"))
      (node (ref "IC22") (pin "18") (pinfunction "8D_18") (pintype "input"))
      (node (ref "IC22") (pin "19") (pinfunction "8Q_19") (pintype "tri_state"))
      (node (ref "IC23") (pin "18") (pinfunction "8D_18") (pintype "input"))
      (node (ref "IC23") (pin "19") (pinfunction "8Q_19") (pintype "tri_state"))
      (node (ref "IC8") (pin "18") (pinfunction "8D_18") (pintype "input"))
      (node (ref "IC8") (pin "19") (pinfunction "8Q_19") (pintype "tri_state"))
      (node (ref "IC9") (pin "18") (pinfunction "8D_18") (pintype "input"))
      (node (ref "IC9") (pin "19") (pinfunction "8Q_19") (pintype "tri_state"))
      (node (ref "X1") (pin "A26") (pinfunction "B_A26") (pintype "passive"))
    )
    (net (code "63") (name "DATA8") (class "Default")
      (node (ref "X1") (pin "A27") (pinfunction "B_A27") (pintype "passive"))
    )
    (net (code "64") (name "DATA9") (class "Default")
      (node (ref "X1") (pin "A28") (pinfunction "B_A28") (pintype "passive"))
    )
    (net (code "65") (name "DATA10") (class "Default")
      (node (ref "X1") (pin "A29") (pinfunction "B_A29") (pintype "passive"))
    )
    (net (code "66") (name "DATA11") (class "Default")
      (node (ref "X1") (pin "A30") (pinfunction "B_A30") (pintype "passive"))
    )
    (net (code "67") (name "DATA12") (class "Default")
      (node (ref "X1") (pin "B3") (pinfunction "B_B3") (pintype "passive"))
    )
    (net (code "68") (name "DATA13") (class "Default")
      (node (ref "X1") (pin "B4") (pinfunction "B_B4") (pintype "passive"))
    )
    (net (code "69") (name "DATA14") (class "Default")
      (node (ref "X1") (pin "B5") (pinfunction "B_B5") (pintype "passive"))
    )
    (net (code "70") (name "DATA15") (class "Default")
      (node (ref "X1") (pin "B6") (pinfunction "B_B6") (pintype "passive"))
    )
    (net (code "71") (name "GND") (class "Default")
      (node (ref "C1") (pin "2") (pinfunction "2_2") (pintype "passive"))
      (node (ref "C10") (pin "2") (pinfunction "2_2") (pintype "passive"))
      (node (ref "C11") (pin "2") (pinfunction "2_2") (pintype "passive"))
      (node (ref "C12") (pin "2") (pinfunction "2_2") (pintype "passive"))
      (node (ref "C13") (pin "2") (pinfunction "2_2") (pintype "passive"))
      (node (ref "C14") (pin "2") (pinfunction "2_2") (pintype "passive"))
      (node (ref "C15") (pin "2") (pinfunction "2_2") (pintype "passive"))
      (node (ref "C16") (pin "2") (pinfunction "2_2") (pintype "passive"))
      (node (ref "C17") (pin "2") (pinfunction "2_2") (pintype "passive"))
      (node (ref "C18") (pin "2") (pinfunction "2_2") (pintype "passive"))
      (node (ref "C19") (pin "2") (pinfunction "2_2") (pintype "passive"))
      (node (ref "C2") (pin "2") (pinfunction "2_2") (pintype "passive"))
      (node (ref "C20") (pin "2") (pinfunction "2_2") (pintype "passive"))
      (node (ref "C21") (pin "2") (pinfunction "2_2") (pintype "passive"))
      (node (ref "C22") (pin "2") (pinfunction "2_2") (pintype "passive"))
      (node (ref "C23") (pin "2") (pinfunction "2_2") (pintype "passive"))
      (node (ref "C24") (pin "2") (pinfunction "2_2") (pintype "passive"))
      (node (ref "C3") (pin "2") (pinfunction "2_2") (pintype "passive"))
      (node (ref "C4") (pin "2") (pinfunction "2_2") (pintype "passive"))
      (node (ref "C5") (pin "2") (pinfunction "2_2") (pintype "passive"))
      (node (ref "C6") (pin "2") (pinfunction "2_2") (pintype "passive"))
      (node (ref "C7") (pin "2") (pinfunction "2_2") (pintype "passive"))
      (node (ref "C8") (pin "2") (pinfunction "2_2") (pintype "passive"))
      (node (ref "C9") (pin "2") (pinfunction "2_2") (pintype "passive"))
      (node (ref "IC4") (pin "2") (pinfunction "A<B_I_2") (pintype "input"))
      (node (ref "IC4") (pin "4") (pinfunction "A>B_I_4") (pintype "input"))
      (node (ref "PWR") (pin "K") (pinfunction "C_K") (pintype "passive"))
      (node (ref "RN1") (pin "1") (pinfunction "1_1") (pintype "passive"))
      (node (ref "V1") (pin "7") (pinfunction "-UB_7") (pintype "power_in"))
      (node (ref "X1") (pin "A1") (pinfunction "B_A1") (pintype "passive"))
      (node (ref "X1") (pin "A32") (pinfunction "B_A32") (pintype "passive"))
      (node (ref "X1") (pin "B1") (pinfunction "B_B1") (pintype "passive"))
      (node (ref "X1") (pin "B32") (pinfunction "B_B32") (pintype "passive"))
      (node (ref "X1") (pin "C1") (pinfunction "B_C1") (pintype "passive"))
      (node (ref "X1") (pin "C32") (pinfunction "B_C32") (pintype "passive"))
    )
    (net (code "72") (name "IN") (class "Default")
      (node (ref "X1") (pin "C26") (pinfunction "B_C26") (pintype "passive"))
    )
    (net (code "73") (name "IO-ADDR0") (class "Default")
      (node (ref "X1") (pin "C7") (pinfunction "B_C7") (pintype "passive"))
    )
    (net (code "74") (name "IO-ADDR1") (class "Default")
      (node (ref "X1") (pin "C8") (pinfunction "B_C8") (pintype "passive"))
    )
    (net (code "75") (name "IO-ADDR2") (class "Default")
      (node (ref "X1") (pin "C9") (pinfunction "B_C9") (pintype "passive"))
    )
    (net (code "76") (name "IO-ADDR3") (class "Default")
      (node (ref "X1") (pin "C10") (pinfunction "B_C10") (pintype "passive"))
    )
    (net (code "77") (name "Net-(IC1A-O)") (class "Default")
      (node (ref "IC1") (pin "10") (pinfunction "I1_10") (pintype "input"))
      (node (ref "IC1") (pin "11") (pinfunction "I2_11") (pintype "input"))
      (node (ref "IC1") (pin "12") (pinfunction "O_12") (pintype "output"))
      (node (ref "IC1") (pin "9") (pinfunction "I0_9") (pintype "input"))
    )
    (net (code "78") (name "Net-(IC1B-O)") (class "Default")
      (node (ref "IC1") (pin "6") (pinfunction "O_6") (pintype "output"))
      (node (ref "IC3") (pin "5") (pinfunction "G2B_5") (pintype "input"))
    )
    (net (code "79") (name "Net-(IC1C-O)") (class "Default")
      (node (ref "IC1") (pin "8") (pinfunction "O_8") (pintype "output"))
      (node (ref "IC2") (pin "4") (pinfunction "G2A_4") (pintype "input"))
      (node (ref "IC3") (pin "4") (pinfunction "G2A_4") (pintype "input"))
    )
    (net (code "80") (name "Net-(IC2A-G1)") (class "Default")
      (node (ref "BRD-SEL") (pin "1") (pinfunction "1_1") (pintype "passive"))
      (node (ref "IC2") (pin "6") (pinfunction "G1_6") (pintype "input"))
      (node (ref "IC3") (pin "6") (pinfunction "G1_6") (pintype "input"))
      (node (ref "IC4") (pin "6") (pinfunction "A=B_O_6") (pintype "output"))
      (node (ref "IC5") (pin "6") (pinfunction "G1_6") (pintype "input"))
      (node (ref "IC6") (pin "6") (pinfunction "G1_6") (pintype "input"))
    )
    (net (code "81") (name "Net-(IC4A-A=B_I)") (class "Default")
      (node (ref "IC4") (pin "3") (pinfunction "A=B_I_3") (pintype "input"))
      (node (ref "V1") (pin "13") (pinfunction "W_13") (pintype "output"))
    )
    (net (code "82") (name "Net-(IC4A-B0)") (class "Default")
      (node (ref "IC4") (pin "9") (pinfunction "B0_9") (pintype "input"))
      (node (ref "RN1") (pin "2") (pinfunction "2_2") (pintype "passive"))
      (node (ref "SW1") (pin "8") (pinfunction "8_8") (pintype "passive"))
    )
    (net (code "83") (name "Net-(IC4A-B1)") (class "Default")
      (node (ref "IC4") (pin "11") (pinfunction "B1_11") (pintype "input"))
      (node (ref "RN1") (pin "3") (pinfunction "3_3") (pintype "passive"))
      (node (ref "SW1") (pin "7") (pinfunction "7_7") (pintype "passive"))
    )
    (net (code "84") (name "Net-(IC4A-B2)") (class "Default")
      (node (ref "IC4") (pin "14") (pinfunction "B2_14") (pintype "input"))
      (node (ref "RN1") (pin "4") (pinfunction "4_4") (pintype "passive"))
      (node (ref "SW1") (pin "6") (pinfunction "6_6") (pintype "passive"))
    )
    (net (code "85") (name "Net-(IC4A-B3)") (class "Default")
      (node (ref "IC4") (pin "1") (pinfunction "B3_1") (pintype "input"))
      (node (ref "RN1") (pin "5") (pinfunction "5_5") (pintype "passive"))
      (node (ref "SW1") (pin "5") (pinfunction "5_5") (pintype "passive"))
    )
    (net (code "86") (name "Net-(IC5A-G2A)") (class "Default")
      (node (ref "IC5") (pin "4") (pinfunction "G2A_4") (pintype "input"))
      (node (ref "IC6") (pin "4") (pinfunction "G2A_4") (pintype "input"))
      (node (ref "IC7") (pin "8") (pinfunction "O_8") (pintype "output"))
    )
    (net (code "87") (name "Net-(IC6A-G2B)") (class "Default")
      (node (ref "IC6") (pin "5") (pinfunction "G2B_5") (pintype "input"))
      (node (ref "IC7") (pin "6") (pinfunction "O_6") (pintype "output"))
    )
    (net (code "88") (name "Net-(IC7A-O)") (class "Default")
      (node (ref "IC7") (pin "10") (pinfunction "I1_10") (pintype "input"))
      (node (ref "IC7") (pin "11") (pinfunction "I2_11") (pintype "input"))
      (node (ref "IC7") (pin "12") (pinfunction "O_12") (pintype "output"))
      (node (ref "IC7") (pin "9") (pinfunction "I0_9") (pintype "input"))
    )
    (net (code "89") (name "Net-(PWR-PadA)") (class "Default")
      (node (ref "PWR") (pin "A") (pinfunction "A_A") (pintype "passive"))
      (node (ref "R1") (pin "1") (pinfunction "1_1") (pintype "passive"))
    )
    (net (code "90") (name "Net-(RD1-PadA)") (class "Default")
      (node (ref "RD1") (pin "A") (pinfunction "A_A") (pintype "passive"))
      (node (ref "RN2") (pin "2") (pinfunction "2_2") (pintype "passive"))
    )
    (net (code "91") (name "Net-(RD2-PadA)") (class "Default")
      (node (ref "RD2") (pin "A") (pinfunction "A_A") (pintype "passive"))
      (node (ref "RN2") (pin "3") (pinfunction "3_3") (pintype "passive"))
    )
    (net (code "92") (name "Net-(RD3-PadA)") (class "Default")
      (node (ref "RD3") (pin "A") (pinfunction "A_A") (pintype "passive"))
      (node (ref "RN2") (pin "4") (pinfunction "4_4") (pintype "passive"))
    )
    (net (code "93") (name "Net-(RD4-PadA)") (class "Default")
      (node (ref "RD4") (pin "A") (pinfunction "A_A") (pintype "passive"))
      (node (ref "RN2") (pin "5") (pinfunction "5_5") (pintype "passive"))
    )
    (net (code "94") (name "Net-(RD5-PadA)") (class "Default")
      (node (ref "RD5") (pin "A") (pinfunction "A_A") (pintype "passive"))
      (node (ref "RN2") (pin "6") (pinfunction "6_6") (pintype "passive"))
    )
    (net (code "95") (name "Net-(RD6-PadA)") (class "Default")
      (node (ref "RD6") (pin "A") (pinfunction "A_A") (pintype "passive"))
      (node (ref "RN2") (pin "7") (pinfunction "7_7") (pintype "passive"))
    )
    (net (code "96") (name "Net-(RD7-PadA)") (class "Default")
      (node (ref "RD7") (pin "A") (pinfunction "A_A") (pintype "passive"))
      (node (ref "RN2") (pin "8") (pinfunction "8_8") (pintype "passive"))
    )
    (net (code "97") (name "Net-(RD8-PadA)") (class "Default")
      (node (ref "RD8") (pin "A") (pinfunction "A_A") (pintype "passive"))
      (node (ref "RN2") (pin "9") (pinfunction "9_9") (pintype "passive"))
    )
    (net (code "98") (name "Net-(RD9-PadA)") (class "Default")
      (node (ref "RD9") (pin "A") (pinfunction "A_A") (pintype "passive"))
      (node (ref "RN4") (pin "2") (pinfunction "2_2") (pintype "passive"))
    )
    (net (code "99") (name "Net-(RD10-PadA)") (class "Default")
      (node (ref "RD10") (pin "A") (pinfunction "A_A") (pintype "passive"))
      (node (ref "RN4") (pin "3") (pinfunction "3_3") (pintype "passive"))
    )
    (net (code "100") (name "Net-(RD11-PadA)") (class "Default")
      (node (ref "RD11") (pin "A") (pinfunction "A_A") (pintype "passive"))
      (node (ref "RN4") (pin "4") (pinfunction "4_4") (pintype "passive"))
    )
    (net (code "101") (name "Net-(RD12-PadA)") (class "Default")
      (node (ref "RD12") (pin "A") (pinfunction "A_A") (pintype "passive"))
      (node (ref "RN4") (pin "5") (pinfunction "5_5") (pintype "passive"))
    )
    (net (code "102") (name "Net-(RD13-PadA)") (class "Default")
      (node (ref "RD13") (pin "A") (pinfunction "A_A") (pintype "passive"))
      (node (ref "RN4") (pin "6") (pinfunction "6_6") (pintype "passive"))
    )
    (net (code "103") (name "Net-(RD14-PadA)") (class "Default")
      (node (ref "RD14") (pin "A") (pinfunction "A_A") (pintype "passive"))
      (node (ref "RN4") (pin "7") (pinfunction "7_7") (pintype "passive"))
    )
    (net (code "104") (name "Net-(RD15-PadA)") (class "Default")
      (node (ref "RD15") (pin "A") (pinfunction "A_A") (pintype "passive"))
      (node (ref "RN4") (pin "8") (pinfunction "8_8") (pintype "passive"))
    )
    (net (code "105") (name "Net-(RD16-PadA)") (class "Default")
      (node (ref "RD16") (pin "A") (pinfunction "A_A") (pintype "passive"))
      (node (ref "RN4") (pin "9") (pinfunction "9_9") (pintype "passive"))
    )
    (net (code "106") (name "Net-(RN3-Pad2)") (class "Default")
      (node (ref "RN3") (pin "2") (pinfunction "2_2") (pintype "passive"))
      (node (ref "WR1") (pin "A") (pinfunction "A_A") (pintype "passive"))
    )
    (net (code "107") (name "Net-(RN3-Pad3)") (class "Default")
      (node (ref "RN3") (pin "3") (pinfunction "3_3") (pintype "passive"))
      (node (ref "WR2") (pin "A") (pinfunction "A_A") (pintype "passive"))
    )
    (net (code "108") (name "Net-(RN3-Pad4)") (class "Default")
      (node (ref "RN3") (pin "4") (pinfunction "4_4") (pintype "passive"))
      (node (ref "WR3") (pin "A") (pinfunction "A_A") (pintype "passive"))
    )
    (net (code "109") (name "Net-(RN3-Pad5)") (class "Default")
      (node (ref "RN3") (pin "5") (pinfunction "5_5") (pintype "passive"))
      (node (ref "WR4") (pin "A") (pinfunction "A_A") (pintype "passive"))
    )
    (net (code "110") (name "Net-(RN3-Pad6)") (class "Default")
      (node (ref "RN3") (pin "6") (pinfunction "6_6") (pintype "passive"))
      (node (ref "WR5") (pin "A") (pinfunction "A_A") (pintype "passive"))
    )
    (net (code "111") (name "Net-(RN3-Pad7)") (class "Default")
      (node (ref "RN3") (pin "7") (pinfunction "7_7") (pintype "passive"))
      (node (ref "WR6") (pin "A") (pinfunction "A_A") (pintype "passive"))
    )
    (net (code "112") (name "Net-(RN3-Pad8)") (class "Default")
      (node (ref "RN3") (pin "8") (pinfunction "8_8") (pintype "passive"))
      (node (ref "WR7") (pin "A") (pinfunction "A_A") (pintype "passive"))
    )
    (net (code "113") (name "Net-(RN3-Pad9)") (class "Default")
      (node (ref "RN3") (pin "9") (pinfunction "9_9") (pintype "passive"))
      (node (ref "WR8") (pin "A") (pinfunction "A_A") (pintype "passive"))
    )
    (net (code "114") (name "Net-(RN5-Pad2)") (class "Default")
      (node (ref "RN5") (pin "2") (pinfunction "2_2") (pintype "passive"))
      (node (ref "WR9") (pin "A") (pinfunction "A_A") (pintype "passive"))
    )
    (net (code "115") (name "Net-(RN5-Pad3)") (class "Default")
      (node (ref "RN5") (pin "3") (pinfunction "3_3") (pintype "passive"))
      (node (ref "WR10") (pin "A") (pinfunction "A_A") (pintype "passive"))
    )
    (net (code "116") (name "Net-(RN5-Pad4)") (class "Default")
      (node (ref "RN5") (pin "4") (pinfunction "4_4") (pintype "passive"))
      (node (ref "WR11") (pin "A") (pinfunction "A_A") (pintype "passive"))
    )
    (net (code "117") (name "Net-(RN5-Pad5)") (class "Default")
      (node (ref "RN5") (pin "5") (pinfunction "5_5") (pintype "passive"))
      (node (ref "WR12") (pin "A") (pinfunction "A_A") (pintype "passive"))
    )
    (net (code "118") (name "Net-(RN5-Pad6)") (class "Default")
      (node (ref "RN5") (pin "6") (pinfunction "6_6") (pintype "passive"))
      (node (ref "WR13") (pin "A") (pinfunction "A_A") (pintype "passive"))
    )
    (net (code "119") (name "Net-(RN5-Pad7)") (class "Default")
      (node (ref "RN5") (pin "7") (pinfunction "7_7") (pintype "passive"))
      (node (ref "WR14") (pin "A") (pinfunction "A_A") (pintype "passive"))
    )
    (net (code "120") (name "Net-(RN5-Pad8)") (class "Default")
      (node (ref "RN5") (pin "8") (pinfunction "8_8") (pintype "passive"))
      (node (ref "WR15") (pin "A") (pinfunction "A_A") (pintype "passive"))
    )
    (net (code "121") (name "Net-(RN5-Pad9)") (class "Default")
      (node (ref "RN5") (pin "9") (pinfunction "9_9") (pintype "passive"))
      (node (ref "WR16") (pin "A") (pinfunction "A_A") (pintype "passive"))
    )
    (net (code "122") (name "OUT") (class "Default")
      (node (ref "X1") (pin "C27") (pinfunction "B_C27") (pintype "passive"))
    )
    (net (code "123") (name "RD0") (class "Default")
      (node (ref "IC2") (pin "15") (pinfunction "Y0_15") (pintype "output"))
      (node (ref "IC8") (pin "1") (pinfunction "OC_1") (pintype "input"))
      (node (ref "RD1") (pin "K") (pinfunction "C_K") (pintype "passive"))
    )
    (net (code "124") (name "RD1") (class "Default")
      (node (ref "IC2") (pin "14") (pinfunction "Y1_14") (pintype "output"))
      (node (ref "IC9") (pin "1") (pinfunction "OC_1") (pintype "input"))
      (node (ref "RD2") (pin "K") (pinfunction "C_K") (pintype "passive"))
    )
    (net (code "125") (name "RD2") (class "Default")
      (node (ref "IC10") (pin "1") (pinfunction "OC_1") (pintype "input"))
      (node (ref "IC2") (pin "13") (pinfunction "Y2_13") (pintype "output"))
      (node (ref "RD3") (pin "K") (pinfunction "C_K") (pintype "passive"))
    )
    (net (code "126") (name "RD3") (class "Default")
      (node (ref "IC11") (pin "1") (pinfunction "OC_1") (pintype "input"))
      (node (ref "IC2") (pin "12") (pinfunction "Y3_12") (pintype "output"))
      (node (ref "RD4") (pin "K") (pinfunction "C_K") (pintype "passive"))
    )
    (net (code "127") (name "RD4") (class "Default")
      (node (ref "IC12") (pin "1") (pinfunction "OC_1") (pintype "input"))
      (node (ref "IC2") (pin "11") (pinfunction "Y4_11") (pintype "output"))
      (node (ref "RD5") (pin "K") (pinfunction "C_K") (pintype "passive"))
    )
    (net (code "128") (name "RD5") (class "Default")
      (node (ref "IC13") (pin "1") (pinfunction "OC_1") (pintype "input"))
      (node (ref "IC2") (pin "10") (pinfunction "Y5_10") (pintype "output"))
      (node (ref "RD6") (pin "K") (pinfunction "C_K") (pintype "passive"))
    )
    (net (code "129") (name "RD6") (class "Default")
      (node (ref "IC14") (pin "1") (pinfunction "OC_1") (pintype "input"))
      (node (ref "IC2") (pin "9") (pinfunction "Y6_9") (pintype "output"))
      (node (ref "RD7") (pin "K") (pinfunction "C_K") (pintype "passive"))
    )
    (net (code "130") (name "RD7") (class "Default")
      (node (ref "IC15") (pin "1") (pinfunction "OC_1") (pintype "input"))
      (node (ref "IC2") (pin "7") (pinfunction "Y7_7") (pintype "output"))
      (node (ref "RD8") (pin "K") (pinfunction "C_K") (pintype "passive"))
    )
    (net (code "131") (name "RD8") (class "Default")
      (node (ref "IC16") (pin "1") (pinfunction "OC_1") (pintype "input"))
      (node (ref "IC3") (pin "15") (pinfunction "Y0_15") (pintype "output"))
      (node (ref "RD9") (pin "K") (pinfunction "C_K") (pintype "passive"))
    )
    (net (code "132") (name "RD9") (class "Default")
      (node (ref "IC17") (pin "1") (pinfunction "OC_1") (pintype "input"))
      (node (ref "IC3") (pin "14") (pinfunction "Y1_14") (pintype "output"))
      (node (ref "RD10") (pin "K") (pinfunction "C_K") (pintype "passive"))
    )
    (net (code "133") (name "RD10") (class "Default")
      (node (ref "IC18") (pin "1") (pinfunction "OC_1") (pintype "input"))
      (node (ref "IC3") (pin "13") (pinfunction "Y2_13") (pintype "output"))
      (node (ref "RD11") (pin "K") (pinfunction "C_K") (pintype "passive"))
    )
    (net (code "134") (name "RD11") (class "Default")
      (node (ref "IC19") (pin "1") (pinfunction "OC_1") (pintype "input"))
      (node (ref "IC3") (pin "12") (pinfunction "Y3_12") (pintype "output"))
      (node (ref "RD12") (pin "K") (pinfunction "C_K") (pintype "passive"))
    )
    (net (code "135") (name "RD12") (class "Default")
      (node (ref "IC20") (pin "1") (pinfunction "OC_1") (pintype "input"))
      (node (ref "IC3") (pin "11") (pinfunction "Y4_11") (pintype "output"))
      (node (ref "RD13") (pin "K") (pinfunction "C_K") (pintype "passive"))
    )
    (net (code "136") (name "RD13") (class "Default")
      (node (ref "IC21") (pin "1") (pinfunction "OC_1") (pintype "input"))
      (node (ref "IC3") (pin "10") (pinfunction "Y5_10") (pintype "output"))
      (node (ref "RD14") (pin "K") (pinfunction "C_K") (pintype "passive"))
    )
    (net (code "137") (name "RD14") (class "Default")
      (node (ref "IC22") (pin "1") (pinfunction "OC_1") (pintype "input"))
      (node (ref "IC3") (pin "9") (pinfunction "Y6_9") (pintype "output"))
      (node (ref "RD15") (pin "K") (pinfunction "C_K") (pintype "passive"))
    )
    (net (code "138") (name "RD15") (class "Default")
      (node (ref "IC23") (pin "1") (pinfunction "OC_1") (pintype "input"))
      (node (ref "IC3") (pin "7") (pinfunction "Y7_7") (pintype "output"))
      (node (ref "RD16") (pin "K") (pinfunction "C_K") (pintype "passive"))
    )
    (net (code "139") (name "REG-LD-ID0") (class "Default")
      (node (ref "X1") (pin "B13") (pinfunction "B_B13") (pintype "passive"))
    )
    (net (code "140") (name "REG-LD-ID1") (class "Default")
      (node (ref "X1") (pin "B14") (pinfunction "B_B14") (pintype "passive"))
    )
    (net (code "141") (name "REG-LD-ID2") (class "Default")
      (node (ref "X1") (pin "B15") (pinfunction "B_B15") (pintype "passive"))
    )
    (net (code "142") (name "REG-LD-ID3") (class "Default")
      (node (ref "X1") (pin "B16") (pinfunction "B_B16") (pintype "passive"))
    )
    (net (code "143") (name "REG-RD-ID0") (class "Default")
      (node (ref "X1") (pin "B9") (pinfunction "B_B9") (pintype "passive"))
    )
    (net (code "144") (name "REG-RD-ID1") (class "Default")
      (node (ref "X1") (pin "B10") (pinfunction "B_B10") (pintype "passive"))
    )
    (net (code "145") (name "REG-RD-ID2") (class "Default")
      (node (ref "X1") (pin "B11") (pinfunction "B_B11") (pintype "passive"))
    )
    (net (code "146") (name "REG-RD-ID3") (class "Default")
      (node (ref "X1") (pin "B12") (pinfunction "B_B12") (pintype "passive"))
    )
    (net (code "147") (name "VCC") (class "Default")
      (node (ref "C1") (pin "1") (pinfunction "1_1") (pintype "passive"))
      (node (ref "C10") (pin "1") (pinfunction "1_1") (pintype "passive"))
      (node (ref "C11") (pin "1") (pinfunction "1_1") (pintype "passive"))
      (node (ref "C12") (pin "1") (pinfunction "1_1") (pintype "passive"))
      (node (ref "C13") (pin "1") (pinfunction "1_1") (pintype "passive"))
      (node (ref "C14") (pin "1") (pinfunction "1_1") (pintype "passive"))
      (node (ref "C15") (pin "1") (pinfunction "1_1") (pintype "passive"))
      (node (ref "C16") (pin "1") (pinfunction "1_1") (pintype "passive"))
      (node (ref "C17") (pin "1") (pinfunction "1_1") (pintype "passive"))
      (node (ref "C18") (pin "1") (pinfunction "1_1") (pintype "passive"))
      (node (ref "C19") (pin "1") (pinfunction "1_1") (pintype "passive"))
      (node (ref "C2") (pin "1") (pinfunction "1_1") (pintype "passive"))
      (node (ref "C20") (pin "1") (pinfunction "1_1") (pintype "passive"))
      (node (ref "C21") (pin "1") (pinfunction "1_1") (pintype "passive"))
      (node (ref "C22") (pin "1") (pinfunction "1_1") (pintype "passive"))
      (node (ref "C23") (pin "1") (pinfunction "1_1") (pintype "passive"))
      (node (ref "C24") (pin "1") (pinfunction "1_1") (pintype "passive"))
      (node (ref "C3") (pin "1") (pinfunction "1_1") (pintype "passive"))
      (node (ref "C4") (pin "1") (pinfunction "1_1") (pintype "passive"))
      (node (ref "C5") (pin "1") (pinfunction "1_1") (pintype "passive"))
      (node (ref "C6") (pin "1") (pinfunction "1_1") (pintype "passive"))
      (node (ref "C7") (pin "1") (pinfunction "1_1") (pintype "passive"))
      (node (ref "C8") (pin "1") (pinfunction "1_1") (pintype "passive"))
      (node (ref "C9") (pin "1") (pinfunction "1_1") (pintype "passive"))
      (node (ref "R1") (pin "2") (pinfunction "2_2") (pintype "passive"))
      (node (ref "RN2") (pin "1") (pinfunction "1_1") (pintype "passive"))
      (node (ref "RN3") (pin "1") (pinfunction "1_1") (pintype "passive"))
      (node (ref "RN4") (pin "1") (pinfunction "1_1") (pintype "passive"))
      (node (ref "RN5") (pin "1") (pinfunction "1_1") (pintype "passive"))
      (node (ref "SW1") (pin "1") (pinfunction "1_1") (pintype "passive"))
      (node (ref "SW1") (pin "2") (pinfunction "2_2") (pintype "passive"))
      (node (ref "SW1") (pin "3") (pinfunction "3_3") (pintype "passive"))
      (node (ref "SW1") (pin "4") (pinfunction "4_4") (pintype "passive"))
      (node (ref "V1") (pin "14") (pinfunction "+UB_14") (pintype "power_in"))
      (node (ref "X1") (pin "A2") (pinfunction "B_A2") (pintype "passive"))
      (node (ref "X1") (pin "A31") (pinfunction "B_A31") (pintype "passive"))
      (node (ref "X1") (pin "B2") (pinfunction "B_B2") (pintype "passive"))
      (node (ref "X1") (pin "B31") (pinfunction "B_B31") (pintype "passive"))
      (node (ref "X1") (pin "C2") (pinfunction "B_C2") (pintype "passive"))
      (node (ref "X1") (pin "C31") (pinfunction "B_C31") (pintype "passive"))
    )
    (net (code "148") (name "WR0") (class "Default")
      (node (ref "IC5") (pin "15") (pinfunction "Y0_15") (pintype "output"))
      (node (ref "IC8") (pin "11") (pinfunction "CLK_11") (pintype "input"))
      (node (ref "WR1") (pin "K") (pinfunction "C_K") (pintype "passive"))
    )
    (net (code "149") (name "WR1") (class "Default")
      (node (ref "IC5") (pin "14") (pinfunction "Y1_14") (pintype "output"))
      (node (ref "IC9") (pin "11") (pinfunction "CLK_11") (pintype "input"))
      (node (ref "WR2") (pin "K") (pinfunction "C_K") (pintype "passive"))
    )
    (net (code "150") (name "WR2") (class "Default")
      (node (ref "IC10") (pin "11") (pinfunction "CLK_11") (pintype "input"))
      (node (ref "IC5") (pin "13") (pinfunction "Y2_13") (pintype "output"))
      (node (ref "WR3") (pin "K") (pinfunction "C_K") (pintype "passive"))
    )
    (net (code "151") (name "WR3") (class "Default")
      (node (ref "IC11") (pin "11") (pinfunction "CLK_11") (pintype "input"))
      (node (ref "IC5") (pin "12") (pinfunction "Y3_12") (pintype "output"))
      (node (ref "WR4") (pin "K") (pinfunction "C_K") (pintype "passive"))
    )
    (net (code "152") (name "WR4") (class "Default")
      (node (ref "IC12") (pin "11") (pinfunction "CLK_11") (pintype "input"))
      (node (ref "IC5") (pin "11") (pinfunction "Y4_11") (pintype "output"))
      (node (ref "WR5") (pin "K") (pinfunction "C_K") (pintype "passive"))
    )
    (net (code "153") (name "WR5") (class "Default")
      (node (ref "IC13") (pin "11") (pinfunction "CLK_11") (pintype "input"))
      (node (ref "IC5") (pin "10") (pinfunction "Y5_10") (pintype "output"))
      (node (ref "WR6") (pin "K") (pinfunction "C_K") (pintype "passive"))
    )
    (net (code "154") (name "WR6") (class "Default")
      (node (ref "IC14") (pin "11") (pinfunction "CLK_11") (pintype "input"))
      (node (ref "IC5") (pin "9") (pinfunction "Y6_9") (pintype "output"))
      (node (ref "WR7") (pin "K") (pinfunction "C_K") (pintype "passive"))
    )
    (net (code "155") (name "WR7") (class "Default")
      (node (ref "IC15") (pin "11") (pinfunction "CLK_11") (pintype "input"))
      (node (ref "IC5") (pin "7") (pinfunction "Y7_7") (pintype "output"))
      (node (ref "WR8") (pin "K") (pinfunction "C_K") (pintype "passive"))
    )
    (net (code "156") (name "WR8") (class "Default")
      (node (ref "IC16") (pin "11") (pinfunction "CLK_11") (pintype "input"))
      (node (ref "IC6") (pin "15") (pinfunction "Y0_15") (pintype "output"))
      (node (ref "WR9") (pin "K") (pinfunction "C_K") (pintype "passive"))
    )
    (net (code "157") (name "WR9") (class "Default")
      (node (ref "IC17") (pin "11") (pinfunction "CLK_11") (pintype "input"))
      (node (ref "IC6") (pin "14") (pinfunction "Y1_14") (pintype "output"))
      (node (ref "WR10") (pin "K") (pinfunction "C_K") (pintype "passive"))
    )
    (net (code "158") (name "WR10") (class "Default")
      (node (ref "IC18") (pin "11") (pinfunction "CLK_11") (pintype "input"))
      (node (ref "IC6") (pin "13") (pinfunction "Y2_13") (pintype "output"))
      (node (ref "WR11") (pin "K") (pinfunction "C_K") (pintype "passive"))
    )
    (net (code "159") (name "WR11") (class "Default")
      (node (ref "IC19") (pin "11") (pinfunction "CLK_11") (pintype "input"))
      (node (ref "IC6") (pin "12") (pinfunction "Y3_12") (pintype "output"))
      (node (ref "WR12") (pin "K") (pinfunction "C_K") (pintype "passive"))
    )
    (net (code "160") (name "WR12") (class "Default")
      (node (ref "IC20") (pin "11") (pinfunction "CLK_11") (pintype "input"))
      (node (ref "IC6") (pin "11") (pinfunction "Y4_11") (pintype "output"))
      (node (ref "WR13") (pin "K") (pinfunction "C_K") (pintype "passive"))
    )
    (net (code "161") (name "WR13") (class "Default")
      (node (ref "IC21") (pin "11") (pinfunction "CLK_11") (pintype "input"))
      (node (ref "IC6") (pin "10") (pinfunction "Y5_10") (pintype "output"))
      (node (ref "WR14") (pin "K") (pinfunction "C_K") (pintype "passive"))
    )
    (net (code "162") (name "WR14") (class "Default")
      (node (ref "IC22") (pin "11") (pinfunction "CLK_11") (pintype "input"))
      (node (ref "IC6") (pin "9") (pinfunction "Y6_9") (pintype "output"))
      (node (ref "WR15") (pin "K") (pinfunction "C_K") (pintype "passive"))
    )
    (net (code "163") (name "WR15") (class "Default")
      (node (ref "IC23") (pin "11") (pinfunction "CLK_11") (pintype "input"))
      (node (ref "IC6") (pin "7") (pinfunction "Y7_7") (pintype "output"))
      (node (ref "WR16") (pin "K") (pinfunction "C_K") (pintype "passive"))
    )
    (net (code "164") (name "unconnected-(IC4A-A<B_O-Pad7)") (class "Default")
      (node (ref "IC4") (pin "7") (pinfunction "A<B_O_7") (pintype "output"))
    )
    (net (code "165") (name "unconnected-(IC4A-A>B_O-Pad5)") (class "Default")
      (node (ref "IC4") (pin "5") (pinfunction "A>B_O_5") (pintype "output"))
    )
    (net (code "166") (name "unconnected-(V1C-Y-Pad1)") (class "Default")
      (node (ref "V1") (pin "1") (pinfunction "Y_1") (pintype "output"))
    )
  )
)
